# cube.net
KiCad netlist of a schematic drawn in Altium Designer
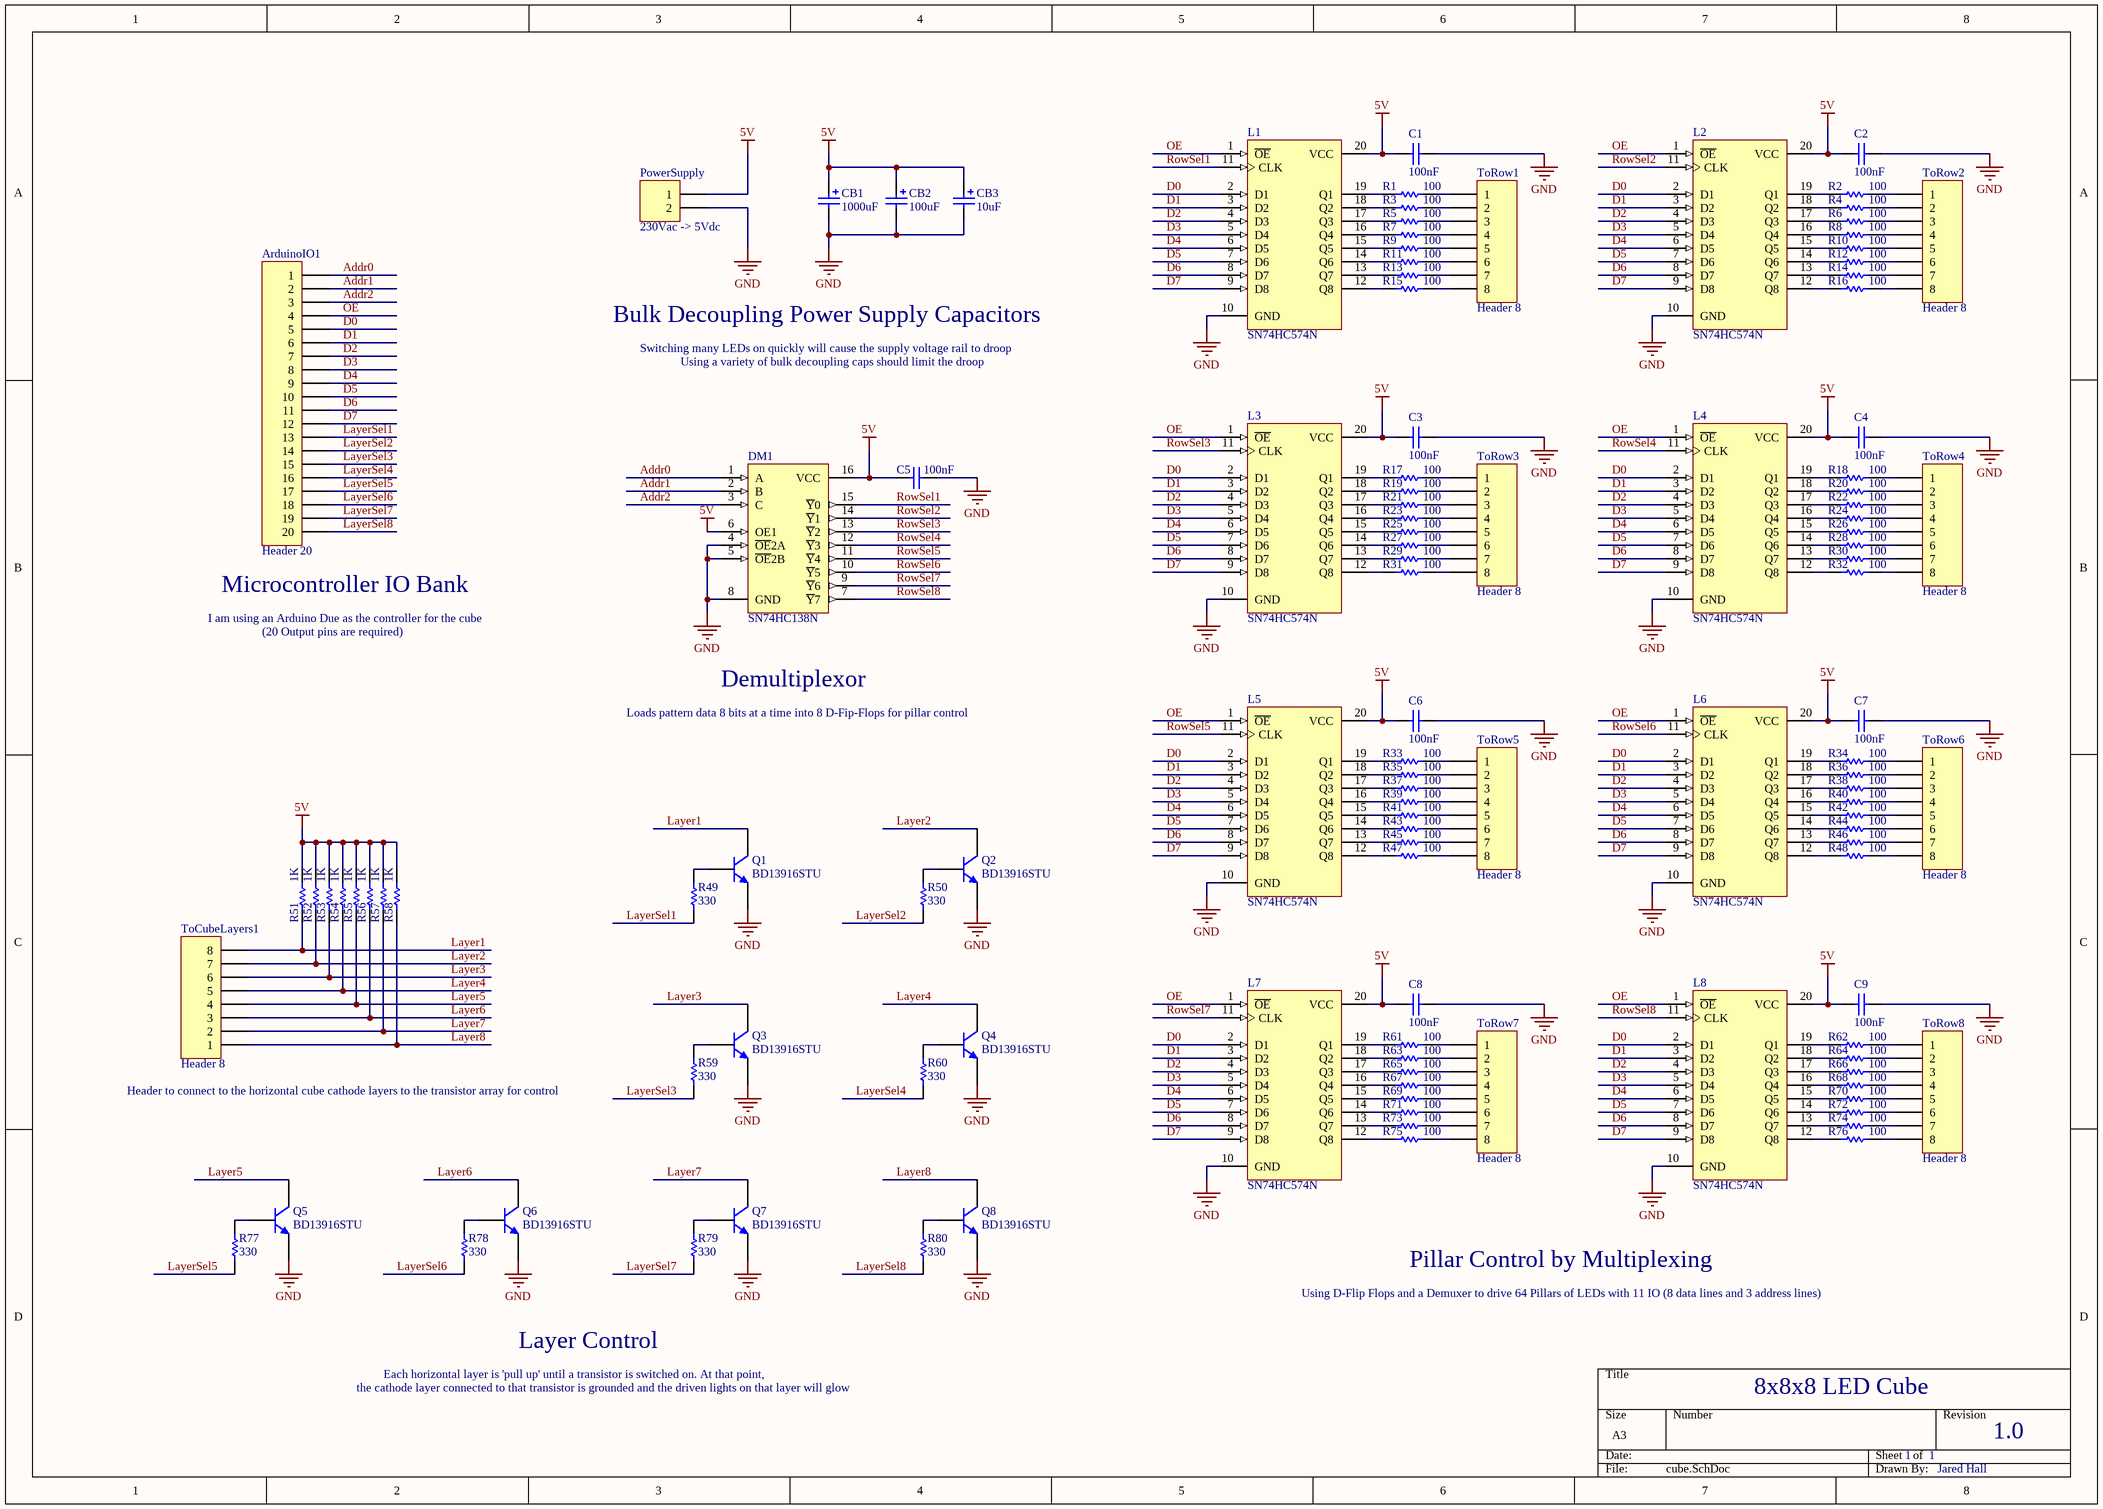
[diagram p0: cube.SchDoc]

(export (version "E")
  (design (tool "Eeschema 10.0.6"))
  (components
    (comp (ref "ArduinoIO1")
      (value "Header 20")
      (footprint "HDR1X20")
      (description "Header, 20-Pin")
      (fields (field (name "PUBLISHER") "Altium Limited"))
      (libsource (lib "Miscellaneous Connectors") (part "Header 20"))
    )
    (comp (ref "C1")
      (value "100nF")
      (footprint "RAD-0.3")
      (description "Capacitor")
      (fields (field (name "Comment") "Cap") (field (name "PUBLISHER") "Altium Limited"))
      (libsource (lib "Miscellaneous Devices") (part "Cap"))
    )
    (comp (ref "C2")
      (value "100nF")
      (footprint "RAD-0.3")
      (description "Capacitor")
      (fields (field (name "Comment") "Cap") (field (name "PUBLISHER") "Altium Limited"))
      (libsource (lib "Miscellaneous Devices") (part "Cap"))
    )
    (comp (ref "C3")
      (value "100nF")
      (footprint "RAD-0.3")
      (description "Capacitor")
      (fields (field (name "Comment") "Cap") (field (name "PUBLISHER") "Altium Limited"))
      (libsource (lib "Miscellaneous Devices") (part "Cap"))
    )
    (comp (ref "C4")
      (value "100nF")
      (footprint "RAD-0.3")
      (description "Capacitor")
      (fields (field (name "Comment") "Cap") (field (name "PUBLISHER") "Altium Limited"))
      (libsource (lib "Miscellaneous Devices") (part "Cap"))
    )
    (comp (ref "C5")
      (value "100nF")
      (footprint "RAD-0.3")
      (description "Capacitor")
      (fields (field (name "Comment") "Cap") (field (name "PUBLISHER") "Altium Limited"))
      (libsource (lib "Miscellaneous Devices") (part "Cap"))
    )
    (comp (ref "C6")
      (value "100nF")
      (footprint "RAD-0.3")
      (description "Capacitor")
      (fields (field (name "Comment") "Cap") (field (name "PUBLISHER") "Altium Limited"))
      (libsource (lib "Miscellaneous Devices") (part "Cap"))
    )
    (comp (ref "C7")
      (value "100nF")
      (footprint "RAD-0.3")
      (description "Capacitor")
      (fields (field (name "Comment") "Cap") (field (name "PUBLISHER") "Altium Limited"))
      (libsource (lib "Miscellaneous Devices") (part "Cap"))
    )
    (comp (ref "C8")
      (value "100nF")
      (footprint "RAD-0.3")
      (description "Capacitor")
      (fields (field (name "Comment") "Cap") (field (name "PUBLISHER") "Altium Limited"))
      (libsource (lib "Miscellaneous Devices") (part "Cap"))
    )
    (comp (ref "C9")
      (value "100nF")
      (footprint "RAD-0.3")
      (description "Capacitor")
      (fields (field (name "Comment") "Cap") (field (name "PUBLISHER") "Altium Limited"))
      (libsource (lib "Miscellaneous Devices") (part "Cap"))
    )
    (comp (ref "CB1")
      (value "1000uF")
      (footprint "POLAR0.8")
      (description "Polarized Capacitor (Axial)")
      (fields (field (name "Comment") "Cap Pol2") (field (name "PUBLISHER") "Altium Limited"))
      (libsource (lib "Miscellaneous Devices") (part "Cap Pol2"))
    )
    (comp (ref "CB2")
      (value "100uF")
      (footprint "POLAR0.8")
      (description "Polarized Capacitor (Axial)")
      (fields (field (name "Comment") "Cap Pol2") (field (name "PUBLISHER") "Altium Limited"))
      (libsource (lib "Miscellaneous Devices") (part "Cap Pol2"))
    )
    (comp (ref "CB3")
      (value "10uF")
      (footprint "POLAR0.8")
      (description "Polarized Capacitor (Axial)")
      (fields (field (name "Comment") "Cap Pol2") (field (name "PUBLISHER") "Altium Limited"))
      (libsource (lib "Miscellaneous Devices") (part "Cap Pol2"))
    )
    (comp (ref "DM1")
      (value "SN74HC138N")
      (footprint "N016")
      (description "3-Line to 8-Line Decoder / Demultiplexer")
      (fields (field (name "PUBLISHER") "Altium Limited"))
      (libsource (lib "TI Logic Decoder Demux") (part "SN74HC138N"))
    )
    (comp (ref "L1")
      (value "SN74HC574N")
      (footprint "N020")
      (description "Octal Edge-Triggered D-Type Flip-Flop with 3-State Outputs")
      (fields (field (name "PUBLISHER") "Altium Limited"))
      (libsource (lib "TI Logic Flip-Flop") (part "SN74HC574N"))
    )
    (comp (ref "L2")
      (value "SN74HC574N")
      (footprint "N020")
      (description "Octal Edge-Triggered D-Type Flip-Flop with 3-State Outputs")
      (fields (field (name "PUBLISHER") "Altium Limited"))
      (libsource (lib "TI Logic Flip-Flop") (part "SN74HC574N"))
    )
    (comp (ref "L3")
      (value "SN74HC574N")
      (footprint "N020")
      (description "Octal Edge-Triggered D-Type Flip-Flop with 3-State Outputs")
      (fields (field (name "PUBLISHER") "Altium Limited"))
      (libsource (lib "TI Logic Flip-Flop") (part "SN74HC574N"))
    )
    (comp (ref "L4")
      (value "SN74HC574N")
      (footprint "N020")
      (description "Octal Edge-Triggered D-Type Flip-Flop with 3-State Outputs")
      (fields (field (name "PUBLISHER") "Altium Limited"))
      (libsource (lib "TI Logic Flip-Flop") (part "SN74HC574N"))
    )
    (comp (ref "L5")
      (value "SN74HC574N")
      (footprint "N020")
      (description "Octal Edge-Triggered D-Type Flip-Flop with 3-State Outputs")
      (fields (field (name "PUBLISHER") "Altium Limited"))
      (libsource (lib "TI Logic Flip-Flop") (part "SN74HC574N"))
    )
    (comp (ref "L6")
      (value "SN74HC574N")
      (footprint "N020")
      (description "Octal Edge-Triggered D-Type Flip-Flop with 3-State Outputs")
      (fields (field (name "PUBLISHER") "Altium Limited"))
      (libsource (lib "TI Logic Flip-Flop") (part "SN74HC574N"))
    )
    (comp (ref "L7")
      (value "SN74HC574N")
      (footprint "N020")
      (description "Octal Edge-Triggered D-Type Flip-Flop with 3-State Outputs")
      (fields (field (name "PUBLISHER") "Altium Limited"))
      (libsource (lib "TI Logic Flip-Flop") (part "SN74HC574N"))
    )
    (comp (ref "L8")
      (value "SN74HC574N")
      (footprint "N020")
      (description "Octal Edge-Triggered D-Type Flip-Flop with 3-State Outputs")
      (fields (field (name "PUBLISHER") "Altium Limited"))
      (libsource (lib "TI Logic Flip-Flop") (part "SN74HC574N"))
    )
    (comp (ref "PowerSupply")
      (value "230Vac -> 5Vdc")
      (footprint "HDR1X2")
      (description "Header, 2-Pin")
      (fields (field (name "PUBLISHER") "Altium Limited"))
      (libsource (lib "Miscellaneous Connectors") (part "Header 2"))
    )
    (comp (ref "Q1")
      (value "BD13916STU")
      (footprint "TO-226-AA")
      (description "NPN Bipolar Transistor")
      (fields (field (name "PUBLISHER") "Altium Limited"))
      (libsource (lib "Miscellaneous Devices") (part "NPN"))
    )
    (comp (ref "Q2")
      (value "BD13916STU")
      (footprint "TO-226-AA")
      (description "NPN Bipolar Transistor")
      (fields (field (name "PUBLISHER") "Altium Limited"))
      (libsource (lib "Miscellaneous Devices") (part "NPN"))
    )
    (comp (ref "Q3")
      (value "BD13916STU")
      (footprint "TO-226-AA")
      (description "NPN Bipolar Transistor")
      (fields (field (name "PUBLISHER") "Altium Limited"))
      (libsource (lib "Miscellaneous Devices") (part "NPN"))
    )
    (comp (ref "Q4")
      (value "BD13916STU")
      (footprint "TO-226-AA")
      (description "NPN Bipolar Transistor")
      (fields (field (name "PUBLISHER") "Altium Limited"))
      (libsource (lib "Miscellaneous Devices") (part "NPN"))
    )
    (comp (ref "Q5")
      (value "BD13916STU")
      (footprint "TO-226-AA")
      (description "NPN Bipolar Transistor")
      (fields (field (name "PUBLISHER") "Altium Limited"))
      (libsource (lib "Miscellaneous Devices") (part "NPN"))
    )
    (comp (ref "Q6")
      (value "BD13916STU")
      (footprint "TO-226-AA")
      (description "NPN Bipolar Transistor")
      (fields (field (name "PUBLISHER") "Altium Limited"))
      (libsource (lib "Miscellaneous Devices") (part "NPN"))
    )
    (comp (ref "Q7")
      (value "BD13916STU")
      (footprint "TO-226-AA")
      (description "NPN Bipolar Transistor")
      (fields (field (name "PUBLISHER") "Altium Limited"))
      (libsource (lib "Miscellaneous Devices") (part "NPN"))
    )
    (comp (ref "Q8")
      (value "BD13916STU")
      (footprint "TO-226-AA")
      (description "NPN Bipolar Transistor")
      (fields (field (name "PUBLISHER") "Altium Limited"))
      (libsource (lib "Miscellaneous Devices") (part "NPN"))
    )
    (comp (ref "R1")
      (value "100")
      (footprint "AXIAL-0.3")
      (description "Resistor")
      (fields (field (name "Comment") "Res1") (field (name "PUBLISHER") "Altium Limited"))
      (libsource (lib "Miscellaneous Devices") (part "Res1"))
    )
    (comp (ref "R2")
      (value "100")
      (footprint "AXIAL-0.3")
      (description "Resistor")
      (fields (field (name "Comment") "Res1") (field (name "PUBLISHER") "Altium Limited"))
      (libsource (lib "Miscellaneous Devices") (part "Res1"))
    )
    (comp (ref "R3")
      (value "100")
      (footprint "AXIAL-0.3")
      (description "Resistor")
      (fields (field (name "Comment") "Res1") (field (name "PUBLISHER") "Altium Limited"))
      (libsource (lib "Miscellaneous Devices") (part "Res1"))
    )
    (comp (ref "R4")
      (value "100")
      (footprint "AXIAL-0.3")
      (description "Resistor")
      (fields (field (name "Comment") "Res1") (field (name "PUBLISHER") "Altium Limited"))
      (libsource (lib "Miscellaneous Devices") (part "Res1"))
    )
    (comp (ref "R5")
      (value "100")
      (footprint "AXIAL-0.3")
      (description "Resistor")
      (fields (field (name "Comment") "Res1") (field (name "PUBLISHER") "Altium Limited"))
      (libsource (lib "Miscellaneous Devices") (part "Res1"))
    )
    (comp (ref "R6")
      (value "100")
      (footprint "AXIAL-0.3")
      (description "Resistor")
      (fields (field (name "Comment") "Res1") (field (name "PUBLISHER") "Altium Limited"))
      (libsource (lib "Miscellaneous Devices") (part "Res1"))
    )
    (comp (ref "R7")
      (value "100")
      (footprint "AXIAL-0.3")
      (description "Resistor")
      (fields (field (name "Comment") "Res1") (field (name "PUBLISHER") "Altium Limited"))
      (libsource (lib "Miscellaneous Devices") (part "Res1"))
    )
    (comp (ref "R8")
      (value "100")
      (footprint "AXIAL-0.3")
      (description "Resistor")
      (fields (field (name "Comment") "Res1") (field (name "PUBLISHER") "Altium Limited"))
      (libsource (lib "Miscellaneous Devices") (part "Res1"))
    )
    (comp (ref "R9")
      (value "100")
      (footprint "AXIAL-0.3")
      (description "Resistor")
      (fields (field (name "Comment") "Res1") (field (name "PUBLISHER") "Altium Limited"))
      (libsource (lib "Miscellaneous Devices") (part "Res1"))
    )
    (comp (ref "R10")
      (value "100")
      (footprint "AXIAL-0.3")
      (description "Resistor")
      (fields (field (name "Comment") "Res1") (field (name "PUBLISHER") "Altium Limited"))
      (libsource (lib "Miscellaneous Devices") (part "Res1"))
    )
    (comp (ref "R11")
      (value "100")
      (footprint "AXIAL-0.3")
      (description "Resistor")
      (fields (field (name "Comment") "Res1") (field (name "PUBLISHER") "Altium Limited"))
      (libsource (lib "Miscellaneous Devices") (part "Res1"))
    )
    (comp (ref "R12")
      (value "100")
      (footprint "AXIAL-0.3")
      (description "Resistor")
      (fields (field (name "Comment") "Res1") (field (name "PUBLISHER") "Altium Limited"))
      (libsource (lib "Miscellaneous Devices") (part "Res1"))
    )
    (comp (ref "R13")
      (value "100")
      (footprint "AXIAL-0.3")
      (description "Resistor")
      (fields (field (name "Comment") "Res1") (field (name "PUBLISHER") "Altium Limited"))
      (libsource (lib "Miscellaneous Devices") (part "Res1"))
    )
    (comp (ref "R14")
      (value "100")
      (footprint "AXIAL-0.3")
      (description "Resistor")
      (fields (field (name "Comment") "Res1") (field (name "PUBLISHER") "Altium Limited"))
      (libsource (lib "Miscellaneous Devices") (part "Res1"))
    )
    (comp (ref "R15")
      (value "100")
      (footprint "AXIAL-0.3")
      (description "Resistor")
      (fields (field (name "Comment") "Res1") (field (name "PUBLISHER") "Altium Limited"))
      (libsource (lib "Miscellaneous Devices") (part "Res1"))
    )
    (comp (ref "R16")
      (value "100")
      (footprint "AXIAL-0.3")
      (description "Resistor")
      (fields (field (name "Comment") "Res1") (field (name "PUBLISHER") "Altium Limited"))
      (libsource (lib "Miscellaneous Devices") (part "Res1"))
    )
    (comp (ref "R17")
      (value "100")
      (footprint "AXIAL-0.3")
      (description "Resistor")
      (fields (field (name "Comment") "Res1") (field (name "PUBLISHER") "Altium Limited"))
      (libsource (lib "Miscellaneous Devices") (part "Res1"))
    )
    (comp (ref "R18")
      (value "100")
      (footprint "AXIAL-0.3")
      (description "Resistor")
      (fields (field (name "Comment") "Res1") (field (name "PUBLISHER") "Altium Limited"))
      (libsource (lib "Miscellaneous Devices") (part "Res1"))
    )
    (comp (ref "R19")
      (value "100")
      (footprint "AXIAL-0.3")
      (description "Resistor")
      (fields (field (name "Comment") "Res1") (field (name "PUBLISHER") "Altium Limited"))
      (libsource (lib "Miscellaneous Devices") (part "Res1"))
    )
    (comp (ref "R20")
      (value "100")
      (footprint "AXIAL-0.3")
      (description "Resistor")
      (fields (field (name "Comment") "Res1") (field (name "PUBLISHER") "Altium Limited"))
      (libsource (lib "Miscellaneous Devices") (part "Res1"))
    )
    (comp (ref "R21")
      (value "100")
      (footprint "AXIAL-0.3")
      (description "Resistor")
      (fields (field (name "Comment") "Res1") (field (name "PUBLISHER") "Altium Limited"))
      (libsource (lib "Miscellaneous Devices") (part "Res1"))
    )
    (comp (ref "R22")
      (value "100")
      (footprint "AXIAL-0.3")
      (description "Resistor")
      (fields (field (name "Comment") "Res1") (field (name "PUBLISHER") "Altium Limited"))
      (libsource (lib "Miscellaneous Devices") (part "Res1"))
    )
    (comp (ref "R23")
      (value "100")
      (footprint "AXIAL-0.3")
      (description "Resistor")
      (fields (field (name "Comment") "Res1") (field (name "PUBLISHER") "Altium Limited"))
      (libsource (lib "Miscellaneous Devices") (part "Res1"))
    )
    (comp (ref "R24")
      (value "100")
      (footprint "AXIAL-0.3")
      (description "Resistor")
      (fields (field (name "Comment") "Res1") (field (name "PUBLISHER") "Altium Limited"))
      (libsource (lib "Miscellaneous Devices") (part "Res1"))
    )
    (comp (ref "R25")
      (value "100")
      (footprint "AXIAL-0.3")
      (description "Resistor")
      (fields (field (name "Comment") "Res1") (field (name "PUBLISHER") "Altium Limited"))
      (libsource (lib "Miscellaneous Devices") (part "Res1"))
    )
    (comp (ref "R26")
      (value "100")
      (footprint "AXIAL-0.3")
      (description "Resistor")
      (fields (field (name "Comment") "Res1") (field (name "PUBLISHER") "Altium Limited"))
      (libsource (lib "Miscellaneous Devices") (part "Res1"))
    )
    (comp (ref "R27")
      (value "100")
      (footprint "AXIAL-0.3")
      (description "Resistor")
      (fields (field (name "Comment") "Res1") (field (name "PUBLISHER") "Altium Limited"))
      (libsource (lib "Miscellaneous Devices") (part "Res1"))
    )
    (comp (ref "R28")
      (value "100")
      (footprint "AXIAL-0.3")
      (description "Resistor")
      (fields (field (name "Comment") "Res1") (field (name "PUBLISHER") "Altium Limited"))
      (libsource (lib "Miscellaneous Devices") (part "Res1"))
    )
    (comp (ref "R29")
      (value "100")
      (footprint "AXIAL-0.3")
      (description "Resistor")
      (fields (field (name "Comment") "Res1") (field (name "PUBLISHER") "Altium Limited"))
      (libsource (lib "Miscellaneous Devices") (part "Res1"))
    )
    (comp (ref "R30")
      (value "100")
      (footprint "AXIAL-0.3")
      (description "Resistor")
      (fields (field (name "Comment") "Res1") (field (name "PUBLISHER") "Altium Limited"))
      (libsource (lib "Miscellaneous Devices") (part "Res1"))
    )
    (comp (ref "R31")
      (value "100")
      (footprint "AXIAL-0.3")
      (description "Resistor")
      (fields (field (name "Comment") "Res1") (field (name "PUBLISHER") "Altium Limited"))
      (libsource (lib "Miscellaneous Devices") (part "Res1"))
    )
    (comp (ref "R32")
      (value "100")
      (footprint "AXIAL-0.3")
      (description "Resistor")
      (fields (field (name "Comment") "Res1") (field (name "PUBLISHER") "Altium Limited"))
      (libsource (lib "Miscellaneous Devices") (part "Res1"))
    )
    (comp (ref "R33")
      (value "100")
      (footprint "AXIAL-0.3")
      (description "Resistor")
      (fields (field (name "Comment") "Res1") (field (name "PUBLISHER") "Altium Limited"))
      (libsource (lib "Miscellaneous Devices") (part "Res1"))
    )
    (comp (ref "R34")
      (value "100")
      (footprint "AXIAL-0.3")
      (description "Resistor")
      (fields (field (name "Comment") "Res1") (field (name "PUBLISHER") "Altium Limited"))
      (libsource (lib "Miscellaneous Devices") (part "Res1"))
    )
    (comp (ref "R35")
      (value "100")
      (footprint "AXIAL-0.3")
      (description "Resistor")
      (fields (field (name "Comment") "Res1") (field (name "PUBLISHER") "Altium Limited"))
      (libsource (lib "Miscellaneous Devices") (part "Res1"))
    )
    (comp (ref "R36")
      (value "100")
      (footprint "AXIAL-0.3")
      (description "Resistor")
      (fields (field (name "Comment") "Res1") (field (name "PUBLISHER") "Altium Limited"))
      (libsource (lib "Miscellaneous Devices") (part "Res1"))
    )
    (comp (ref "R37")
      (value "100")
      (footprint "AXIAL-0.3")
      (description "Resistor")
      (fields (field (name "Comment") "Res1") (field (name "PUBLISHER") "Altium Limited"))
      (libsource (lib "Miscellaneous Devices") (part "Res1"))
    )
    (comp (ref "R38")
      (value "100")
      (footprint "AXIAL-0.3")
      (description "Resistor")
      (fields (field (name "Comment") "Res1") (field (name "PUBLISHER") "Altium Limited"))
      (libsource (lib "Miscellaneous Devices") (part "Res1"))
    )
    (comp (ref "R39")
      (value "100")
      (footprint "AXIAL-0.3")
      (description "Resistor")
      (fields (field (name "Comment") "Res1") (field (name "PUBLISHER") "Altium Limited"))
      (libsource (lib "Miscellaneous Devices") (part "Res1"))
    )
    (comp (ref "R40")
      (value "100")
      (footprint "AXIAL-0.3")
      (description "Resistor")
      (fields (field (name "Comment") "Res1") (field (name "PUBLISHER") "Altium Limited"))
      (libsource (lib "Miscellaneous Devices") (part "Res1"))
    )
    (comp (ref "R41")
      (value "100")
      (footprint "AXIAL-0.3")
      (description "Resistor")
      (fields (field (name "Comment") "Res1") (field (name "PUBLISHER") "Altium Limited"))
      (libsource (lib "Miscellaneous Devices") (part "Res1"))
    )
    (comp (ref "R42")
      (value "100")
      (footprint "AXIAL-0.3")
      (description "Resistor")
      (fields (field (name "Comment") "Res1") (field (name "PUBLISHER") "Altium Limited"))
      (libsource (lib "Miscellaneous Devices") (part "Res1"))
    )
    (comp (ref "R43")
      (value "100")
      (footprint "AXIAL-0.3")
      (description "Resistor")
      (fields (field (name "Comment") "Res1") (field (name "PUBLISHER") "Altium Limited"))
      (libsource (lib "Miscellaneous Devices") (part "Res1"))
    )
    (comp (ref "R44")
      (value "100")
      (footprint "AXIAL-0.3")
      (description "Resistor")
      (fields (field (name "Comment") "Res1") (field (name "PUBLISHER") "Altium Limited"))
      (libsource (lib "Miscellaneous Devices") (part "Res1"))
    )
    (comp (ref "R45")
      (value "100")
      (footprint "AXIAL-0.3")
      (description "Resistor")
      (fields (field (name "Comment") "Res1") (field (name "PUBLISHER") "Altium Limited"))
      (libsource (lib "Miscellaneous Devices") (part "Res1"))
    )
    (comp (ref "R46")
      (value "100")
      (footprint "AXIAL-0.3")
      (description "Resistor")
      (fields (field (name "Comment") "Res1") (field (name "PUBLISHER") "Altium Limited"))
      (libsource (lib "Miscellaneous Devices") (part "Res1"))
    )
    (comp (ref "R47")
      (value "100")
      (footprint "AXIAL-0.3")
      (description "Resistor")
      (fields (field (name "Comment") "Res1") (field (name "PUBLISHER") "Altium Limited"))
      (libsource (lib "Miscellaneous Devices") (part "Res1"))
    )
    (comp (ref "R48")
      (value "100")
      (footprint "AXIAL-0.3")
      (description "Resistor")
      (fields (field (name "Comment") "Res1") (field (name "PUBLISHER") "Altium Limited"))
      (libsource (lib "Miscellaneous Devices") (part "Res1"))
    )
    (comp (ref "R49")
      (value "330")
      (footprint "AXIAL-0.3")
      (description "Resistor")
      (fields (field (name "Comment") "Res1") (field (name "PUBLISHER") "Altium Limited"))
      (libsource (lib "Miscellaneous Devices") (part "Res1"))
    )
    (comp (ref "R50")
      (value "330")
      (footprint "AXIAL-0.3")
      (description "Resistor")
      (fields (field (name "Comment") "Res1") (field (name "PUBLISHER") "Altium Limited"))
      (libsource (lib "Miscellaneous Devices") (part "Res1"))
    )
    (comp (ref "R51")
      (value "1K")
      (footprint "AXIAL-0.3")
      (description "Resistor")
      (fields (field (name "Comment") "Res1") (field (name "PUBLISHER") "Altium Limited"))
      (libsource (lib "Miscellaneous Devices") (part "Res1"))
    )
    (comp (ref "R52")
      (value "1K")
      (footprint "AXIAL-0.3")
      (description "Resistor")
      (fields (field (name "Comment") "Res1") (field (name "PUBLISHER") "Altium Limited"))
      (libsource (lib "Miscellaneous Devices") (part "Res1"))
    )
    (comp (ref "R53")
      (value "1K")
      (footprint "AXIAL-0.3")
      (description "Resistor")
      (fields (field (name "Comment") "Res1") (field (name "PUBLISHER") "Altium Limited"))
      (libsource (lib "Miscellaneous Devices") (part "Res1"))
    )
    (comp (ref "R54")
      (value "1K")
      (footprint "AXIAL-0.3")
      (description "Resistor")
      (fields (field (name "Comment") "Res1") (field (name "PUBLISHER") "Altium Limited"))
      (libsource (lib "Miscellaneous Devices") (part "Res1"))
    )
    (comp (ref "R55")
      (value "1K")
      (footprint "AXIAL-0.3")
      (description "Resistor")
      (fields (field (name "Comment") "Res1") (field (name "PUBLISHER") "Altium Limited"))
      (libsource (lib "Miscellaneous Devices") (part "Res1"))
    )
    (comp (ref "R56")
      (value "1K")
      (footprint "AXIAL-0.3")
      (description "Resistor")
      (fields (field (name "Comment") "Res1") (field (name "PUBLISHER") "Altium Limited"))
      (libsource (lib "Miscellaneous Devices") (part "Res1"))
    )
    (comp (ref "R57")
      (value "1K")
      (footprint "AXIAL-0.3")
      (description "Resistor")
      (fields (field (name "Comment") "Res1") (field (name "PUBLISHER") "Altium Limited"))
      (libsource (lib "Miscellaneous Devices") (part "Res1"))
    )
    (comp (ref "R58")
      (value "1K")
      (footprint "AXIAL-0.3")
      (description "Resistor")
      (fields (field (name "Comment") "Res1") (field (name "PUBLISHER") "Altium Limited"))
      (libsource (lib "Miscellaneous Devices") (part "Res1"))
    )
    (comp (ref "R59")
      (value "330")
      (footprint "AXIAL-0.3")
      (description "Resistor")
      (fields (field (name "Comment") "Res1") (field (name "PUBLISHER") "Altium Limited"))
      (libsource (lib "Miscellaneous Devices") (part "Res1"))
    )
    (comp (ref "R60")
      (value "330")
      (footprint "AXIAL-0.3")
      (description "Resistor")
      (fields (field (name "Comment") "Res1") (field (name "PUBLISHER") "Altium Limited"))
      (libsource (lib "Miscellaneous Devices") (part "Res1"))
    )
    (comp (ref "R61")
      (value "100")
      (footprint "AXIAL-0.3")
      (description "Resistor")
      (fields (field (name "Comment") "Res1") (field (name "PUBLISHER") "Altium Limited"))
      (libsource (lib "Miscellaneous Devices") (part "Res1"))
    )
    (comp (ref "R62")
      (value "100")
      (footprint "AXIAL-0.3")
      (description "Resistor")
      (fields (field (name "Comment") "Res1") (field (name "PUBLISHER") "Altium Limited"))
      (libsource (lib "Miscellaneous Devices") (part "Res1"))
    )
    (comp (ref "R63")
      (value "100")
      (footprint "AXIAL-0.3")
      (description "Resistor")
      (fields (field (name "Comment") "Res1") (field (name "PUBLISHER") "Altium Limited"))
      (libsource (lib "Miscellaneous Devices") (part "Res1"))
    )
    (comp (ref "R64")
      (value "100")
      (footprint "AXIAL-0.3")
      (description "Resistor")
      (fields (field (name "Comment") "Res1") (field (name "PUBLISHER") "Altium Limited"))
      (libsource (lib "Miscellaneous Devices") (part "Res1"))
    )
    (comp (ref "R65")
      (value "100")
      (footprint "AXIAL-0.3")
      (description "Resistor")
      (fields (field (name "Comment") "Res1") (field (name "PUBLISHER") "Altium Limited"))
      (libsource (lib "Miscellaneous Devices") (part "Res1"))
    )
    (comp (ref "R66")
      (value "100")
      (footprint "AXIAL-0.3")
      (description "Resistor")
      (fields (field (name "Comment") "Res1") (field (name "PUBLISHER") "Altium Limited"))
      (libsource (lib "Miscellaneous Devices") (part "Res1"))
    )
    (comp (ref "R67")
      (value "100")
      (footprint "AXIAL-0.3")
      (description "Resistor")
      (fields (field (name "Comment") "Res1") (field (name "PUBLISHER") "Altium Limited"))
      (libsource (lib "Miscellaneous Devices") (part "Res1"))
    )
    (comp (ref "R68")
      (value "100")
      (footprint "AXIAL-0.3")
      (description "Resistor")
      (fields (field (name "Comment") "Res1") (field (name "PUBLISHER") "Altium Limited"))
      (libsource (lib "Miscellaneous Devices") (part "Res1"))
    )
    (comp (ref "R69")
      (value "100")
      (footprint "AXIAL-0.3")
      (description "Resistor")
      (fields (field (name "Comment") "Res1") (field (name "PUBLISHER") "Altium Limited"))
      (libsource (lib "Miscellaneous Devices") (part "Res1"))
    )
    (comp (ref "R70")
      (value "100")
      (footprint "AXIAL-0.3")
      (description "Resistor")
      (fields (field (name "Comment") "Res1") (field (name "PUBLISHER") "Altium Limited"))
      (libsource (lib "Miscellaneous Devices") (part "Res1"))
    )
    (comp (ref "R71")
      (value "100")
      (footprint "AXIAL-0.3")
      (description "Resistor")
      (fields (field (name "Comment") "Res1") (field (name "PUBLISHER") "Altium Limited"))
      (libsource (lib "Miscellaneous Devices") (part "Res1"))
    )
    (comp (ref "R72")
      (value "100")
      (footprint "AXIAL-0.3")
      (description "Resistor")
      (fields (field (name "Comment") "Res1") (field (name "PUBLISHER") "Altium Limited"))
      (libsource (lib "Miscellaneous Devices") (part "Res1"))
    )
    (comp (ref "R73")
      (value "100")
      (footprint "AXIAL-0.3")
      (description "Resistor")
      (fields (field (name "Comment") "Res1") (field (name "PUBLISHER") "Altium Limited"))
      (libsource (lib "Miscellaneous Devices") (part "Res1"))
    )
    (comp (ref "R74")
      (value "100")
      (footprint "AXIAL-0.3")
      (description "Resistor")
      (fields (field (name "Comment") "Res1") (field (name "PUBLISHER") "Altium Limited"))
      (libsource (lib "Miscellaneous Devices") (part "Res1"))
    )
    (comp (ref "R75")
      (value "100")
      (footprint "AXIAL-0.3")
      (description "Resistor")
      (fields (field (name "Comment") "Res1") (field (name "PUBLISHER") "Altium Limited"))
      (libsource (lib "Miscellaneous Devices") (part "Res1"))
    )
    (comp (ref "R76")
      (value "100")
      (footprint "AXIAL-0.3")
      (description "Resistor")
      (fields (field (name "Comment") "Res1") (field (name "PUBLISHER") "Altium Limited"))
      (libsource (lib "Miscellaneous Devices") (part "Res1"))
    )
    (comp (ref "R77")
      (value "330")
      (footprint "AXIAL-0.3")
      (description "Resistor")
      (fields (field (name "Comment") "Res1") (field (name "PUBLISHER") "Altium Limited"))
      (libsource (lib "Miscellaneous Devices") (part "Res1"))
    )
    (comp (ref "R78")
      (value "330")
      (footprint "AXIAL-0.3")
      (description "Resistor")
      (fields (field (name "Comment") "Res1") (field (name "PUBLISHER") "Altium Limited"))
      (libsource (lib "Miscellaneous Devices") (part "Res1"))
    )
    (comp (ref "R79")
      (value "330")
      (footprint "AXIAL-0.3")
      (description "Resistor")
      (fields (field (name "Comment") "Res1") (field (name "PUBLISHER") "Altium Limited"))
      (libsource (lib "Miscellaneous Devices") (part "Res1"))
    )
    (comp (ref "R80")
      (value "330")
      (footprint "AXIAL-0.3")
      (description "Resistor")
      (fields (field (name "Comment") "Res1") (field (name "PUBLISHER") "Altium Limited"))
      (libsource (lib "Miscellaneous Devices") (part "Res1"))
    )
    (comp (ref "ToCubeLayers1")
      (value "Header 8")
      (footprint "HDR1X8")
      (description "Header, 8-Pin")
      (fields (field (name "PUBLISHER") "Altium Limited"))
      (libsource (lib "") (part "Header 8_1"))
    )
    (comp (ref "ToRow1")
      (value "Header 8")
      (footprint "HDR1X8")
      (description "Header, 8-Pin")
      (fields (field (name "PUBLISHER") "Altium Limited"))
      (libsource (lib "Miscellaneous Connectors") (part "Header 8"))
    )
    (comp (ref "ToRow2")
      (value "Header 8")
      (footprint "HDR1X8")
      (description "Header, 8-Pin")
      (fields (field (name "PUBLISHER") "Altium Limited"))
      (libsource (lib "Miscellaneous Connectors") (part "Header 8"))
    )
    (comp (ref "ToRow3")
      (value "Header 8")
      (footprint "HDR1X8")
      (description "Header, 8-Pin")
      (fields (field (name "PUBLISHER") "Altium Limited"))
      (libsource (lib "Miscellaneous Connectors") (part "Header 8"))
    )
    (comp (ref "ToRow4")
      (value "Header 8")
      (footprint "HDR1X8")
      (description "Header, 8-Pin")
      (fields (field (name "PUBLISHER") "Altium Limited"))
      (libsource (lib "Miscellaneous Connectors") (part "Header 8"))
    )
    (comp (ref "ToRow5")
      (value "Header 8")
      (footprint "HDR1X8")
      (description "Header, 8-Pin")
      (fields (field (name "PUBLISHER") "Altium Limited"))
      (libsource (lib "Miscellaneous Connectors") (part "Header 8"))
    )
    (comp (ref "ToRow6")
      (value "Header 8")
      (footprint "HDR1X8")
      (description "Header, 8-Pin")
      (fields (field (name "PUBLISHER") "Altium Limited"))
      (libsource (lib "Miscellaneous Connectors") (part "Header 8"))
    )
    (comp (ref "ToRow7")
      (value "Header 8")
      (footprint "HDR1X8")
      (description "Header, 8-Pin")
      (fields (field (name "PUBLISHER") "Altium Limited"))
      (libsource (lib "Miscellaneous Connectors") (part "Header 8"))
    )
    (comp (ref "ToRow8")
      (value "Header 8")
      (footprint "HDR1X8")
      (description "Header, 8-Pin")
      (fields (field (name "PUBLISHER") "Altium Limited"))
      (libsource (lib "Miscellaneous Connectors") (part "Header 8"))
    )
  )
  (nets
    (net (code "1") (name "/Addr0") (class "Default")
      (node (ref "ArduinoIO1") (pin "1") (pinfunction "1_1") (pintype "passive"))
      (node (ref "DM1") (pin "1") (pinfunction "A_1") (pintype "input"))
    )
    (net (code "2") (name "/Addr1") (class "Default")
      (node (ref "ArduinoIO1") (pin "2") (pinfunction "2_2") (pintype "passive"))
      (node (ref "DM1") (pin "2") (pinfunction "B_2") (pintype "input"))
    )
    (net (code "3") (name "/Addr2") (class "Default")
      (node (ref "ArduinoIO1") (pin "3") (pinfunction "3_3") (pintype "passive"))
      (node (ref "DM1") (pin "3") (pinfunction "C_3") (pintype "input"))
    )
    (net (code "4") (name "/D0") (class "Default")
      (node (ref "ArduinoIO1") (pin "5") (pinfunction "5_5") (pintype "passive"))
      (node (ref "L1") (pin "2") (pinfunction "D1_2") (pintype "input"))
      (node (ref "L2") (pin "2") (pinfunction "D1_2") (pintype "input"))
      (node (ref "L3") (pin "2") (pinfunction "D1_2") (pintype "input"))
      (node (ref "L4") (pin "2") (pinfunction "D1_2") (pintype "input"))
      (node (ref "L5") (pin "2") (pinfunction "D1_2") (pintype "input"))
      (node (ref "L6") (pin "2") (pinfunction "D1_2") (pintype "input"))
      (node (ref "L7") (pin "2") (pinfunction "D1_2") (pintype "input"))
      (node (ref "L8") (pin "2") (pinfunction "D1_2") (pintype "input"))
    )
    (net (code "5") (name "/D1") (class "Default")
      (node (ref "ArduinoIO1") (pin "6") (pinfunction "6_6") (pintype "passive"))
      (node (ref "L1") (pin "3") (pinfunction "D2_3") (pintype "input"))
      (node (ref "L2") (pin "3") (pinfunction "D2_3") (pintype "input"))
      (node (ref "L3") (pin "3") (pinfunction "D2_3") (pintype "input"))
      (node (ref "L4") (pin "3") (pinfunction "D2_3") (pintype "input"))
      (node (ref "L5") (pin "3") (pinfunction "D2_3") (pintype "input"))
      (node (ref "L6") (pin "3") (pinfunction "D2_3") (pintype "input"))
      (node (ref "L7") (pin "3") (pinfunction "D2_3") (pintype "input"))
      (node (ref "L8") (pin "3") (pinfunction "D2_3") (pintype "input"))
    )
    (net (code "6") (name "/D2") (class "Default")
      (node (ref "ArduinoIO1") (pin "7") (pinfunction "7_7") (pintype "passive"))
      (node (ref "L1") (pin "4") (pinfunction "D3_4") (pintype "input"))
      (node (ref "L2") (pin "4") (pinfunction "D3_4") (pintype "input"))
      (node (ref "L3") (pin "4") (pinfunction "D3_4") (pintype "input"))
      (node (ref "L4") (pin "4") (pinfunction "D3_4") (pintype "input"))
      (node (ref "L5") (pin "4") (pinfunction "D3_4") (pintype "input"))
      (node (ref "L6") (pin "4") (pinfunction "D3_4") (pintype "input"))
      (node (ref "L7") (pin "4") (pinfunction "D3_4") (pintype "input"))
      (node (ref "L8") (pin "4") (pinfunction "D3_4") (pintype "input"))
    )
    (net (code "7") (name "/D3") (class "Default")
      (node (ref "ArduinoIO1") (pin "8") (pinfunction "8_8") (pintype "passive"))
      (node (ref "L1") (pin "5") (pinfunction "D4_5") (pintype "input"))
      (node (ref "L2") (pin "5") (pinfunction "D4_5") (pintype "input"))
      (node (ref "L3") (pin "5") (pinfunction "D4_5") (pintype "input"))
      (node (ref "L4") (pin "5") (pinfunction "D4_5") (pintype "input"))
      (node (ref "L5") (pin "5") (pinfunction "D4_5") (pintype "input"))
      (node (ref "L6") (pin "5") (pinfunction "D4_5") (pintype "input"))
      (node (ref "L7") (pin "5") (pinfunction "D4_5") (pintype "input"))
      (node (ref "L8") (pin "5") (pinfunction "D4_5") (pintype "input"))
    )
    (net (code "8") (name "/D4") (class "Default")
      (node (ref "ArduinoIO1") (pin "9") (pinfunction "9_9") (pintype "passive"))
      (node (ref "L1") (pin "6") (pinfunction "D5_6") (pintype "input"))
      (node (ref "L2") (pin "6") (pinfunction "D5_6") (pintype "input"))
      (node (ref "L3") (pin "6") (pinfunction "D5_6") (pintype "input"))
      (node (ref "L4") (pin "6") (pinfunction "D5_6") (pintype "input"))
      (node (ref "L5") (pin "6") (pinfunction "D5_6") (pintype "input"))
      (node (ref "L6") (pin "6") (pinfunction "D5_6") (pintype "input"))
      (node (ref "L7") (pin "6") (pinfunction "D5_6") (pintype "input"))
      (node (ref "L8") (pin "6") (pinfunction "D5_6") (pintype "input"))
    )
    (net (code "9") (name "/D5") (class "Default")
      (node (ref "ArduinoIO1") (pin "10") (pinfunction "10_10") (pintype "passive"))
      (node (ref "L1") (pin "7") (pinfunction "D6_7") (pintype "input"))
      (node (ref "L2") (pin "7") (pinfunction "D6_7") (pintype "input"))
      (node (ref "L3") (pin "7") (pinfunction "D6_7") (pintype "input"))
      (node (ref "L4") (pin "7") (pinfunction "D6_7") (pintype "input"))
      (node (ref "L5") (pin "7") (pinfunction "D6_7") (pintype "input"))
      (node (ref "L6") (pin "7") (pinfunction "D6_7") (pintype "input"))
      (node (ref "L7") (pin "7") (pinfunction "D6_7") (pintype "input"))
      (node (ref "L8") (pin "7") (pinfunction "D6_7") (pintype "input"))
    )
    (net (code "10") (name "/D6") (class "Default")
      (node (ref "ArduinoIO1") (pin "11") (pinfunction "11_11") (pintype "passive"))
      (node (ref "L1") (pin "8") (pinfunction "D7_8") (pintype "input"))
      (node (ref "L2") (pin "8") (pinfunction "D7_8") (pintype "input"))
      (node (ref "L3") (pin "8") (pinfunction "D7_8") (pintype "input"))
      (node (ref "L4") (pin "8") (pinfunction "D7_8") (pintype "input"))
      (node (ref "L5") (pin "8") (pinfunction "D7_8") (pintype "input"))
      (node (ref "L6") (pin "8") (pinfunction "D7_8") (pintype "input"))
      (node (ref "L7") (pin "8") (pinfunction "D7_8") (pintype "input"))
      (node (ref "L8") (pin "8") (pinfunction "D7_8") (pintype "input"))
    )
    (net (code "11") (name "/D7") (class "Default")
      (node (ref "ArduinoIO1") (pin "12") (pinfunction "12_12") (pintype "passive"))
      (node (ref "L1") (pin "9") (pinfunction "D8_9") (pintype "input"))
      (node (ref "L2") (pin "9") (pinfunction "D8_9") (pintype "input"))
      (node (ref "L3") (pin "9") (pinfunction "D8_9") (pintype "input"))
      (node (ref "L4") (pin "9") (pinfunction "D8_9") (pintype "input"))
      (node (ref "L5") (pin "9") (pinfunction "D8_9") (pintype "input"))
      (node (ref "L6") (pin "9") (pinfunction "D8_9") (pintype "input"))
      (node (ref "L7") (pin "9") (pinfunction "D8_9") (pintype "input"))
      (node (ref "L8") (pin "9") (pinfunction "D8_9") (pintype "input"))
    )
    (net (code "12") (name "/Layer1") (class "Default")
      (node (ref "Q1") (pin "1") (pinfunction "C_1") (pintype "passive"))
      (node (ref "R51") (pin "1") (pinfunction "1_1") (pintype "passive"))
      (node (ref "ToCubeLayers1") (pin "8") (pinfunction "8_8") (pintype "passive"))
    )
    (net (code "13") (name "/Layer2") (class "Default")
      (node (ref "Q2") (pin "1") (pinfunction "C_1") (pintype "passive"))
      (node (ref "R52") (pin "1") (pinfunction "1_1") (pintype "passive"))
      (node (ref "ToCubeLayers1") (pin "7") (pinfunction "7_7") (pintype "passive"))
    )
    (net (code "14") (name "/Layer3") (class "Default")
      (node (ref "Q3") (pin "1") (pinfunction "C_1") (pintype "passive"))
      (node (ref "R53") (pin "1") (pinfunction "1_1") (pintype "passive"))
      (node (ref "ToCubeLayers1") (pin "6") (pinfunction "6_6") (pintype "passive"))
    )
    (net (code "15") (name "/Layer4") (class "Default")
      (node (ref "Q4") (pin "1") (pinfunction "C_1") (pintype "passive"))
      (node (ref "R54") (pin "1") (pinfunction "1_1") (pintype "passive"))
      (node (ref "ToCubeLayers1") (pin "5") (pinfunction "5_5") (pintype "passive"))
    )
    (net (code "16") (name "/Layer5") (class "Default")
      (node (ref "Q5") (pin "1") (pinfunction "C_1") (pintype "passive"))
      (node (ref "R55") (pin "1") (pinfunction "1_1") (pintype "passive"))
      (node (ref "ToCubeLayers1") (pin "4") (pinfunction "4_4") (pintype "passive"))
    )
    (net (code "17") (name "/Layer6") (class "Default")
      (node (ref "Q6") (pin "1") (pinfunction "C_1") (pintype "passive"))
      (node (ref "R56") (pin "1") (pinfunction "1_1") (pintype "passive"))
      (node (ref "ToCubeLayers1") (pin "3") (pinfunction "3_3") (pintype "passive"))
    )
    (net (code "18") (name "/Layer7") (class "Default")
      (node (ref "Q7") (pin "1") (pinfunction "C_1") (pintype "passive"))
      (node (ref "R57") (pin "1") (pinfunction "1_1") (pintype "passive"))
      (node (ref "ToCubeLayers1") (pin "2") (pinfunction "2_2") (pintype "passive"))
    )
    (net (code "19") (name "/Layer8") (class "Default")
      (node (ref "Q8") (pin "1") (pinfunction "C_1") (pintype "passive"))
      (node (ref "R58") (pin "1") (pinfunction "1_1") (pintype "passive"))
      (node (ref "ToCubeLayers1") (pin "1") (pinfunction "1_1") (pintype "passive"))
    )
    (net (code "20") (name "/LayerSel1") (class "Default")
      (node (ref "ArduinoIO1") (pin "13") (pinfunction "13_13") (pintype "passive"))
      (node (ref "R49") (pin "1") (pinfunction "1_1") (pintype "passive"))
    )
    (net (code "21") (name "/LayerSel2") (class "Default")
      (node (ref "ArduinoIO1") (pin "14") (pinfunction "14_14") (pintype "passive"))
      (node (ref "R50") (pin "1") (pinfunction "1_1") (pintype "passive"))
    )
    (net (code "22") (name "/LayerSel3") (class "Default")
      (node (ref "ArduinoIO1") (pin "15") (pinfunction "15_15") (pintype "passive"))
      (node (ref "R59") (pin "1") (pinfunction "1_1") (pintype "passive"))
    )
    (net (code "23") (name "/LayerSel4") (class "Default")
      (node (ref "ArduinoIO1") (pin "16") (pinfunction "16_16") (pintype "passive"))
      (node (ref "R60") (pin "1") (pinfunction "1_1") (pintype "passive"))
    )
    (net (code "24") (name "/LayerSel5") (class "Default")
      (node (ref "ArduinoIO1") (pin "17") (pinfunction "17_17") (pintype "passive"))
      (node (ref "R77") (pin "1") (pinfunction "1_1") (pintype "passive"))
    )
    (net (code "25") (name "/LayerSel6") (class "Default")
      (node (ref "ArduinoIO1") (pin "18") (pinfunction "18_18") (pintype "passive"))
      (node (ref "R78") (pin "1") (pinfunction "1_1") (pintype "passive"))
    )
    (net (code "26") (name "/LayerSel7") (class "Default")
      (node (ref "ArduinoIO1") (pin "19") (pinfunction "19_19") (pintype "passive"))
      (node (ref "R79") (pin "1") (pinfunction "1_1") (pintype "passive"))
    )
    (net (code "27") (name "/LayerSel8") (class "Default")
      (node (ref "ArduinoIO1") (pin "20") (pinfunction "20_20") (pintype "passive"))
      (node (ref "R80") (pin "1") (pinfunction "1_1") (pintype "passive"))
    )
    (net (code "28") (name "/OE") (class "Default")
      (node (ref "ArduinoIO1") (pin "4") (pinfunction "4_4") (pintype "passive"))
      (node (ref "L1") (pin "1") (pinfunction "~{OE}_1") (pintype "input"))
      (node (ref "L2") (pin "1") (pinfunction "~{OE}_1") (pintype "input"))
      (node (ref "L3") (pin "1") (pinfunction "~{OE}_1") (pintype "input"))
      (node (ref "L4") (pin "1") (pinfunction "~{OE}_1") (pintype "input"))
      (node (ref "L5") (pin "1") (pinfunction "~{OE}_1") (pintype "input"))
      (node (ref "L6") (pin "1") (pinfunction "~{OE}_1") (pintype "input"))
      (node (ref "L7") (pin "1") (pinfunction "~{OE}_1") (pintype "input"))
      (node (ref "L8") (pin "1") (pinfunction "~{OE}_1") (pintype "input"))
    )
    (net (code "29") (name "/RowSel1") (class "Default")
      (node (ref "DM1") (pin "15") (pinfunction "~{Y}0_15") (pintype "output"))
      (node (ref "L1") (pin "11") (pinfunction "CLK_11") (pintype "input"))
    )
    (net (code "30") (name "/RowSel2") (class "Default")
      (node (ref "DM1") (pin "14") (pinfunction "~{Y}1_14") (pintype "output"))
      (node (ref "L2") (pin "11") (pinfunction "CLK_11") (pintype "input"))
    )
    (net (code "31") (name "/RowSel3") (class "Default")
      (node (ref "DM1") (pin "13") (pinfunction "~{Y}2_13") (pintype "output"))
      (node (ref "L3") (pin "11") (pinfunction "CLK_11") (pintype "input"))
    )
    (net (code "32") (name "/RowSel4") (class "Default")
      (node (ref "DM1") (pin "12") (pinfunction "~{Y}3_12") (pintype "output"))
      (node (ref "L4") (pin "11") (pinfunction "CLK_11") (pintype "input"))
    )
    (net (code "33") (name "/RowSel5") (class "Default")
      (node (ref "DM1") (pin "11") (pinfunction "~{Y}4_11") (pintype "output"))
      (node (ref "L5") (pin "11") (pinfunction "CLK_11") (pintype "input"))
    )
    (net (code "34") (name "/RowSel6") (class "Default")
      (node (ref "DM1") (pin "10") (pinfunction "~{Y}5_10") (pintype "output"))
      (node (ref "L6") (pin "11") (pinfunction "CLK_11") (pintype "input"))
    )
    (net (code "35") (name "/RowSel7") (class "Default")
      (node (ref "DM1") (pin "9") (pinfunction "~{Y}6_9") (pintype "output"))
      (node (ref "L7") (pin "11") (pinfunction "CLK_11") (pintype "input"))
    )
    (net (code "36") (name "/RowSel8") (class "Default")
      (node (ref "DM1") (pin "7") (pinfunction "~{Y}7_7") (pintype "output"))
      (node (ref "L8") (pin "11") (pinfunction "CLK_11") (pintype "input"))
    )
    (net (code "37") (name "5V") (class "Default")
      (node (ref "C1") (pin "1") (pinfunction "1_1") (pintype "passive"))
      (node (ref "C2") (pin "1") (pinfunction "1_1") (pintype "passive"))
      (node (ref "C3") (pin "1") (pinfunction "1_1") (pintype "passive"))
      (node (ref "C4") (pin "1") (pinfunction "1_1") (pintype "passive"))
      (node (ref "C5") (pin "1") (pinfunction "1_1") (pintype "passive"))
      (node (ref "C6") (pin "1") (pinfunction "1_1") (pintype "passive"))
      (node (ref "C7") (pin "1") (pinfunction "1_1") (pintype "passive"))
      (node (ref "C8") (pin "1") (pinfunction "1_1") (pintype "passive"))
      (node (ref "C9") (pin "1") (pinfunction "1_1") (pintype "passive"))
      (node (ref "CB1") (pin "1") (pinfunction "1_1") (pintype "passive"))
      (node (ref "CB2") (pin "1") (pinfunction "1_1") (pintype "passive"))
      (node (ref "CB3") (pin "1") (pinfunction "1_1") (pintype "passive"))
      (node (ref "DM1") (pin "16") (pinfunction "VCC_16") (pintype "power_in"))
      (node (ref "DM1") (pin "6") (pinfunction "OE1_6") (pintype "input"))
      (node (ref "L1") (pin "20") (pinfunction "VCC_20") (pintype "power_in"))
      (node (ref "L2") (pin "20") (pinfunction "VCC_20") (pintype "power_in"))
      (node (ref "L3") (pin "20") (pinfunction "VCC_20") (pintype "power_in"))
      (node (ref "L4") (pin "20") (pinfunction "VCC_20") (pintype "power_in"))
      (node (ref "L5") (pin "20") (pinfunction "VCC_20") (pintype "power_in"))
      (node (ref "L6") (pin "20") (pinfunction "VCC_20") (pintype "power_in"))
      (node (ref "L7") (pin "20") (pinfunction "VCC_20") (pintype "power_in"))
      (node (ref "L8") (pin "20") (pinfunction "VCC_20") (pintype "power_in"))
      (node (ref "PowerSupply") (pin "1") (pinfunction "1_1") (pintype "passive"))
      (node (ref "R51") (pin "2") (pinfunction "2_2") (pintype "passive"))
      (node (ref "R52") (pin "2") (pinfunction "2_2") (pintype "passive"))
      (node (ref "R53") (pin "2") (pinfunction "2_2") (pintype "passive"))
      (node (ref "R54") (pin "2") (pinfunction "2_2") (pintype "passive"))
      (node (ref "R55") (pin "2") (pinfunction "2_2") (pintype "passive"))
      (node (ref "R56") (pin "2") (pinfunction "2_2") (pintype "passive"))
      (node (ref "R57") (pin "2") (pinfunction "2_2") (pintype "passive"))
      (node (ref "R58") (pin "2") (pinfunction "2_2") (pintype "passive"))
    )
    (net (code "38") (name "GND") (class "Default")
      (node (ref "C1") (pin "2") (pinfunction "2_2") (pintype "passive"))
      (node (ref "C2") (pin "2") (pinfunction "2_2") (pintype "passive"))
      (node (ref "C3") (pin "2") (pinfunction "2_2") (pintype "passive"))
      (node (ref "C4") (pin "2") (pinfunction "2_2") (pintype "passive"))
      (node (ref "C5") (pin "2") (pinfunction "2_2") (pintype "passive"))
      (node (ref "C6") (pin "2") (pinfunction "2_2") (pintype "passive"))
      (node (ref "C7") (pin "2") (pinfunction "2_2") (pintype "passive"))
      (node (ref "C8") (pin "2") (pinfunction "2_2") (pintype "passive"))
      (node (ref "C9") (pin "2") (pinfunction "2_2") (pintype "passive"))
      (node (ref "CB1") (pin "2") (pinfunction "2_2") (pintype "passive"))
      (node (ref "CB2") (pin "2") (pinfunction "2_2") (pintype "passive"))
      (node (ref "CB3") (pin "2") (pinfunction "2_2") (pintype "passive"))
      (node (ref "DM1") (pin "4") (pinfunction "~{OE}2A_4") (pintype "input"))
      (node (ref "DM1") (pin "5") (pinfunction "~{OE}2B_5") (pintype "input"))
      (node (ref "DM1") (pin "8") (pinfunction "GND_8") (pintype "power_in"))
      (node (ref "L1") (pin "10") (pinfunction "GND_10") (pintype "power_in"))
      (node (ref "L2") (pin "10") (pinfunction "GND_10") (pintype "power_in"))
      (node (ref "L3") (pin "10") (pinfunction "GND_10") (pintype "power_in"))
      (node (ref "L4") (pin "10") (pinfunction "GND_10") (pintype "power_in"))
      (node (ref "L5") (pin "10") (pinfunction "GND_10") (pintype "power_in"))
      (node (ref "L6") (pin "10") (pinfunction "GND_10") (pintype "power_in"))
      (node (ref "L7") (pin "10") (pinfunction "GND_10") (pintype "power_in"))
      (node (ref "L8") (pin "10") (pinfunction "GND_10") (pintype "power_in"))
      (node (ref "PowerSupply") (pin "2") (pinfunction "2_2") (pintype "passive"))
      (node (ref "Q1") (pin "3") (pinfunction "E_3") (pintype "passive"))
      (node (ref "Q2") (pin "3") (pinfunction "E_3") (pintype "passive"))
      (node (ref "Q3") (pin "3") (pinfunction "E_3") (pintype "passive"))
      (node (ref "Q4") (pin "3") (pinfunction "E_3") (pintype "passive"))
      (node (ref "Q5") (pin "3") (pinfunction "E_3") (pintype "passive"))
      (node (ref "Q6") (pin "3") (pinfunction "E_3") (pintype "passive"))
      (node (ref "Q7") (pin "3") (pinfunction "E_3") (pintype "passive"))
      (node (ref "Q8") (pin "3") (pinfunction "E_3") (pintype "passive"))
    )
    (net (code "39") (name "Net-(L1-Q1)") (class "Default")
      (node (ref "L1") (pin "19") (pinfunction "Q1_19") (pintype "tri_state"))
      (node (ref "R1") (pin "1") (pinfunction "1_1") (pintype "passive"))
    )
    (net (code "40") (name "Net-(L1-Q2)") (class "Default")
      (node (ref "L1") (pin "18") (pinfunction "Q2_18") (pintype "tri_state"))
      (node (ref "R3") (pin "1") (pinfunction "1_1") (pintype "passive"))
    )
    (net (code "41") (name "Net-(L1-Q3)") (class "Default")
      (node (ref "L1") (pin "17") (pinfunction "Q3_17") (pintype "tri_state"))
      (node (ref "R5") (pin "1") (pinfunction "1_1") (pintype "passive"))
    )
    (net (code "42") (name "Net-(L1-Q4)") (class "Default")
      (node (ref "L1") (pin "16") (pinfunction "Q4_16") (pintype "tri_state"))
      (node (ref "R7") (pin "1") (pinfunction "1_1") (pintype "passive"))
    )
    (net (code "43") (name "Net-(L1-Q5)") (class "Default")
      (node (ref "L1") (pin "15") (pinfunction "Q5_15") (pintype "tri_state"))
      (node (ref "R9") (pin "1") (pinfunction "1_1") (pintype "passive"))
    )
    (net (code "44") (name "Net-(L1-Q6)") (class "Default")
      (node (ref "L1") (pin "14") (pinfunction "Q6_14") (pintype "tri_state"))
      (node (ref "R11") (pin "1") (pinfunction "1_1") (pintype "passive"))
    )
    (net (code "45") (name "Net-(L1-Q7)") (class "Default")
      (node (ref "L1") (pin "13") (pinfunction "Q7_13") (pintype "tri_state"))
      (node (ref "R13") (pin "1") (pinfunction "1_1") (pintype "passive"))
    )
    (net (code "46") (name "Net-(L1-Q8)") (class "Default")
      (node (ref "L1") (pin "12") (pinfunction "Q8_12") (pintype "tri_state"))
      (node (ref "R15") (pin "1") (pinfunction "1_1") (pintype "passive"))
    )
    (net (code "47") (name "Net-(L2-Q1)") (class "Default")
      (node (ref "L2") (pin "19") (pinfunction "Q1_19") (pintype "tri_state"))
      (node (ref "R2") (pin "1") (pinfunction "1_1") (pintype "passive"))
    )
    (net (code "48") (name "Net-(L2-Q2)") (class "Default")
      (node (ref "L2") (pin "18") (pinfunction "Q2_18") (pintype "tri_state"))
      (node (ref "R4") (pin "1") (pinfunction "1_1") (pintype "passive"))
    )
    (net (code "49") (name "Net-(L2-Q3)") (class "Default")
      (node (ref "L2") (pin "17") (pinfunction "Q3_17") (pintype "tri_state"))
      (node (ref "R6") (pin "1") (pinfunction "1_1") (pintype "passive"))
    )
    (net (code "50") (name "Net-(L2-Q4)") (class "Default")
      (node (ref "L2") (pin "16") (pinfunction "Q4_16") (pintype "tri_state"))
      (node (ref "R8") (pin "1") (pinfunction "1_1") (pintype "passive"))
    )
    (net (code "51") (name "Net-(L2-Q5)") (class "Default")
      (node (ref "L2") (pin "15") (pinfunction "Q5_15") (pintype "tri_state"))
      (node (ref "R10") (pin "1") (pinfunction "1_1") (pintype "passive"))
    )
    (net (code "52") (name "Net-(L2-Q6)") (class "Default")
      (node (ref "L2") (pin "14") (pinfunction "Q6_14") (pintype "tri_state"))
      (node (ref "R12") (pin "1") (pinfunction "1_1") (pintype "passive"))
    )
    (net (code "53") (name "Net-(L2-Q7)") (class "Default")
      (node (ref "L2") (pin "13") (pinfunction "Q7_13") (pintype "tri_state"))
      (node (ref "R14") (pin "1") (pinfunction "1_1") (pintype "passive"))
    )
    (net (code "54") (name "Net-(L2-Q8)") (class "Default")
      (node (ref "L2") (pin "12") (pinfunction "Q8_12") (pintype "tri_state"))
      (node (ref "R16") (pin "1") (pinfunction "1_1") (pintype "passive"))
    )
    (net (code "55") (name "Net-(L3-Q1)") (class "Default")
      (node (ref "L3") (pin "19") (pinfunction "Q1_19") (pintype "tri_state"))
      (node (ref "R17") (pin "1") (pinfunction "1_1") (pintype "passive"))
    )
    (net (code "56") (name "Net-(L3-Q2)") (class "Default")
      (node (ref "L3") (pin "18") (pinfunction "Q2_18") (pintype "tri_state"))
      (node (ref "R19") (pin "1") (pinfunction "1_1") (pintype "passive"))
    )
    (net (code "57") (name "Net-(L3-Q3)") (class "Default")
      (node (ref "L3") (pin "17") (pinfunction "Q3_17") (pintype "tri_state"))
      (node (ref "R21") (pin "1") (pinfunction "1_1") (pintype "passive"))
    )
    (net (code "58") (name "Net-(L3-Q4)") (class "Default")
      (node (ref "L3") (pin "16") (pinfunction "Q4_16") (pintype "tri_state"))
      (node (ref "R23") (pin "1") (pinfunction "1_1") (pintype "passive"))
    )
    (net (code "59") (name "Net-(L3-Q5)") (class "Default")
      (node (ref "L3") (pin "15") (pinfunction "Q5_15") (pintype "tri_state"))
      (node (ref "R25") (pin "1") (pinfunction "1_1") (pintype "passive"))
    )
    (net (code "60") (name "Net-(L3-Q6)") (class "Default")
      (node (ref "L3") (pin "14") (pinfunction "Q6_14") (pintype "tri_state"))
      (node (ref "R27") (pin "1") (pinfunction "1_1") (pintype "passive"))
    )
    (net (code "61") (name "Net-(L3-Q7)") (class "Default")
      (node (ref "L3") (pin "13") (pinfunction "Q7_13") (pintype "tri_state"))
      (node (ref "R29") (pin "1") (pinfunction "1_1") (pintype "passive"))
    )
    (net (code "62") (name "Net-(L3-Q8)") (class "Default")
      (node (ref "L3") (pin "12") (pinfunction "Q8_12") (pintype "tri_state"))
      (node (ref "R31") (pin "1") (pinfunction "1_1") (pintype "passive"))
    )
    (net (code "63") (name "Net-(L4-Q1)") (class "Default")
      (node (ref "L4") (pin "19") (pinfunction "Q1_19") (pintype "tri_state"))
      (node (ref "R18") (pin "1") (pinfunction "1_1") (pintype "passive"))
    )
    (net (code "64") (name "Net-(L4-Q2)") (class "Default")
      (node (ref "L4") (pin "18") (pinfunction "Q2_18") (pintype "tri_state"))
      (node (ref "R20") (pin "1") (pinfunction "1_1") (pintype "passive"))
    )
    (net (code "65") (name "Net-(L4-Q3)") (class "Default")
      (node (ref "L4") (pin "17") (pinfunction "Q3_17") (pintype "tri_state"))
      (node (ref "R22") (pin "1") (pinfunction "1_1") (pintype "passive"))
    )
    (net (code "66") (name "Net-(L4-Q4)") (class "Default")
      (node (ref "L4") (pin "16") (pinfunction "Q4_16") (pintype "tri_state"))
      (node (ref "R24") (pin "1") (pinfunction "1_1") (pintype "passive"))
    )
    (net (code "67") (name "Net-(L4-Q5)") (class "Default")
      (node (ref "L4") (pin "15") (pinfunction "Q5_15") (pintype "tri_state"))
      (node (ref "R26") (pin "1") (pinfunction "1_1") (pintype "passive"))
    )
    (net (code "68") (name "Net-(L4-Q6)") (class "Default")
      (node (ref "L4") (pin "14") (pinfunction "Q6_14") (pintype "tri_state"))
      (node (ref "R28") (pin "1") (pinfunction "1_1") (pintype "passive"))
    )
    (net (code "69") (name "Net-(L4-Q7)") (class "Default")
      (node (ref "L4") (pin "13") (pinfunction "Q7_13") (pintype "tri_state"))
      (node (ref "R30") (pin "1") (pinfunction "1_1") (pintype "passive"))
    )
    (net (code "70") (name "Net-(L4-Q8)") (class "Default")
      (node (ref "L4") (pin "12") (pinfunction "Q8_12") (pintype "tri_state"))
      (node (ref "R32") (pin "1") (pinfunction "1_1") (pintype "passive"))
    )
    (net (code "71") (name "Net-(L5-Q1)") (class "Default")
      (node (ref "L5") (pin "19") (pinfunction "Q1_19") (pintype "tri_state"))
      (node (ref "R33") (pin "1") (pinfunction "1_1") (pintype "passive"))
    )
    (net (code "72") (name "Net-(L5-Q2)") (class "Default")
      (node (ref "L5") (pin "18") (pinfunction "Q2_18") (pintype "tri_state"))
      (node (ref "R35") (pin "1") (pinfunction "1_1") (pintype "passive"))
    )
    (net (code "73") (name "Net-(L5-Q3)") (class "Default")
      (node (ref "L5") (pin "17") (pinfunction "Q3_17") (pintype "tri_state"))
      (node (ref "R37") (pin "1") (pinfunction "1_1") (pintype "passive"))
    )
    (net (code "74") (name "Net-(L5-Q4)") (class "Default")
      (node (ref "L5") (pin "16") (pinfunction "Q4_16") (pintype "tri_state"))
      (node (ref "R39") (pin "1") (pinfunction "1_1") (pintype "passive"))
    )
    (net (code "75") (name "Net-(L5-Q5)") (class "Default")
      (node (ref "L5") (pin "15") (pinfunction "Q5_15") (pintype "tri_state"))
      (node (ref "R41") (pin "1") (pinfunction "1_1") (pintype "passive"))
    )
    (net (code "76") (name "Net-(L5-Q6)") (class "Default")
      (node (ref "L5") (pin "14") (pinfunction "Q6_14") (pintype "tri_state"))
      (node (ref "R43") (pin "1") (pinfunction "1_1") (pintype "passive"))
    )
    (net (code "77") (name "Net-(L5-Q7)") (class "Default")
      (node (ref "L5") (pin "13") (pinfunction "Q7_13") (pintype "tri_state"))
      (node (ref "R45") (pin "1") (pinfunction "1_1") (pintype "passive"))
    )
    (net (code "78") (name "Net-(L5-Q8)") (class "Default")
      (node (ref "L5") (pin "12") (pinfunction "Q8_12") (pintype "tri_state"))
      (node (ref "R47") (pin "1") (pinfunction "1_1") (pintype "passive"))
    )
    (net (code "79") (name "Net-(L6-Q1)") (class "Default")
      (node (ref "L6") (pin "19") (pinfunction "Q1_19") (pintype "tri_state"))
      (node (ref "R34") (pin "1") (pinfunction "1_1") (pintype "passive"))
    )
    (net (code "80") (name "Net-(L6-Q2)") (class "Default")
      (node (ref "L6") (pin "18") (pinfunction "Q2_18") (pintype "tri_state"))
      (node (ref "R36") (pin "1") (pinfunction "1_1") (pintype "passive"))
    )
    (net (code "81") (name "Net-(L6-Q3)") (class "Default")
      (node (ref "L6") (pin "17") (pinfunction "Q3_17") (pintype "tri_state"))
      (node (ref "R38") (pin "1") (pinfunction "1_1") (pintype "passive"))
    )
    (net (code "82") (name "Net-(L6-Q4)") (class "Default")
      (node (ref "L6") (pin "16") (pinfunction "Q4_16") (pintype "tri_state"))
      (node (ref "R40") (pin "1") (pinfunction "1_1") (pintype "passive"))
    )
    (net (code "83") (name "Net-(L6-Q5)") (class "Default")
      (node (ref "L6") (pin "15") (pinfunction "Q5_15") (pintype "tri_state"))
      (node (ref "R42") (pin "1") (pinfunction "1_1") (pintype "passive"))
    )
    (net (code "84") (name "Net-(L6-Q6)") (class "Default")
      (node (ref "L6") (pin "14") (pinfunction "Q6_14") (pintype "tri_state"))
      (node (ref "R44") (pin "1") (pinfunction "1_1") (pintype "passive"))
    )
    (net (code "85") (name "Net-(L6-Q7)") (class "Default")
      (node (ref "L6") (pin "13") (pinfunction "Q7_13") (pintype "tri_state"))
      (node (ref "R46") (pin "1") (pinfunction "1_1") (pintype "passive"))
    )
    (net (code "86") (name "Net-(L6-Q8)") (class "Default")
      (node (ref "L6") (pin "12") (pinfunction "Q8_12") (pintype "tri_state"))
      (node (ref "R48") (pin "1") (pinfunction "1_1") (pintype "passive"))
    )
    (net (code "87") (name "Net-(L7-Q1)") (class "Default")
      (node (ref "L7") (pin "19") (pinfunction "Q1_19") (pintype "tri_state"))
      (node (ref "R61") (pin "1") (pinfunction "1_1") (pintype "passive"))
    )
    (net (code "88") (name "Net-(L7-Q2)") (class "Default")
      (node (ref "L7") (pin "18") (pinfunction "Q2_18") (pintype "tri_state"))
      (node (ref "R63") (pin "1") (pinfunction "1_1") (pintype "passive"))
    )
    (net (code "89") (name "Net-(L7-Q3)") (class "Default")
      (node (ref "L7") (pin "17") (pinfunction "Q3_17") (pintype "tri_state"))
      (node (ref "R65") (pin "1") (pinfunction "1_1") (pintype "passive"))
    )
    (net (code "90") (name "Net-(L7-Q4)") (class "Default")
      (node (ref "L7") (pin "16") (pinfunction "Q4_16") (pintype "tri_state"))
      (node (ref "R67") (pin "1") (pinfunction "1_1") (pintype "passive"))
    )
    (net (code "91") (name "Net-(L7-Q5)") (class "Default")
      (node (ref "L7") (pin "15") (pinfunction "Q5_15") (pintype "tri_state"))
      (node (ref "R69") (pin "1") (pinfunction "1_1") (pintype "passive"))
    )
    (net (code "92") (name "Net-(L7-Q6)") (class "Default")
      (node (ref "L7") (pin "14") (pinfunction "Q6_14") (pintype "tri_state"))
      (node (ref "R71") (pin "1") (pinfunction "1_1") (pintype "passive"))
    )
    (net (code "93") (name "Net-(L7-Q7)") (class "Default")
      (node (ref "L7") (pin "13") (pinfunction "Q7_13") (pintype "tri_state"))
      (node (ref "R73") (pin "1") (pinfunction "1_1") (pintype "passive"))
    )
    (net (code "94") (name "Net-(L7-Q8)") (class "Default")
      (node (ref "L7") (pin "12") (pinfunction "Q8_12") (pintype "tri_state"))
      (node (ref "R75") (pin "1") (pinfunction "1_1") (pintype "passive"))
    )
    (net (code "95") (name "Net-(L8-Q1)") (class "Default")
      (node (ref "L8") (pin "19") (pinfunction "Q1_19") (pintype "tri_state"))
      (node (ref "R62") (pin "1") (pinfunction "1_1") (pintype "passive"))
    )
    (net (code "96") (name "Net-(L8-Q2)") (class "Default")
      (node (ref "L8") (pin "18") (pinfunction "Q2_18") (pintype "tri_state"))
      (node (ref "R64") (pin "1") (pinfunction "1_1") (pintype "passive"))
    )
    (net (code "97") (name "Net-(L8-Q3)") (class "Default")
      (node (ref "L8") (pin "17") (pinfunction "Q3_17") (pintype "tri_state"))
      (node (ref "R66") (pin "1") (pinfunction "1_1") (pintype "passive"))
    )
    (net (code "98") (name "Net-(L8-Q4)") (class "Default")
      (node (ref "L8") (pin "16") (pinfunction "Q4_16") (pintype "tri_state"))
      (node (ref "R68") (pin "1") (pinfunction "1_1") (pintype "passive"))
    )
    (net (code "99") (name "Net-(L8-Q5)") (class "Default")
      (node (ref "L8") (pin "15") (pinfunction "Q5_15") (pintype "tri_state"))
      (node (ref "R70") (pin "1") (pinfunction "1_1") (pintype "passive"))
    )
    (net (code "100") (name "Net-(L8-Q6)") (class "Default")
      (node (ref "L8") (pin "14") (pinfunction "Q6_14") (pintype "tri_state"))
      (node (ref "R72") (pin "1") (pinfunction "1_1") (pintype "passive"))
    )
    (net (code "101") (name "Net-(L8-Q7)") (class "Default")
      (node (ref "L8") (pin "13") (pinfunction "Q7_13") (pintype "tri_state"))
      (node (ref "R74") (pin "1") (pinfunction "1_1") (pintype "passive"))
    )
    (net (code "102") (name "Net-(L8-Q8)") (class "Default")
      (node (ref "L8") (pin "12") (pinfunction "Q8_12") (pintype "tri_state"))
      (node (ref "R76") (pin "1") (pinfunction "1_1") (pintype "passive"))
    )
    (net (code "103") (name "Net-(Q1-B)") (class "Default")
      (node (ref "Q1") (pin "2") (pinfunction "B_2") (pintype "passive"))
      (node (ref "R49") (pin "2") (pinfunction "2_2") (pintype "passive"))
    )
    (net (code "104") (name "Net-(Q2-B)") (class "Default")
      (node (ref "Q2") (pin "2") (pinfunction "B_2") (pintype "passive"))
      (node (ref "R50") (pin "2") (pinfunction "2_2") (pintype "passive"))
    )
    (net (code "105") (name "Net-(Q3-B)") (class "Default")
      (node (ref "Q3") (pin "2") (pinfunction "B_2") (pintype "passive"))
      (node (ref "R59") (pin "2") (pinfunction "2_2") (pintype "passive"))
    )
    (net (code "106") (name "Net-(Q4-B)") (class "Default")
      (node (ref "Q4") (pin "2") (pinfunction "B_2") (pintype "passive"))
      (node (ref "R60") (pin "2") (pinfunction "2_2") (pintype "passive"))
    )
    (net (code "107") (name "Net-(Q5-B)") (class "Default")
      (node (ref "Q5") (pin "2") (pinfunction "B_2") (pintype "passive"))
      (node (ref "R77") (pin "2") (pinfunction "2_2") (pintype "passive"))
    )
    (net (code "108") (name "Net-(Q6-B)") (class "Default")
      (node (ref "Q6") (pin "2") (pinfunction "B_2") (pintype "passive"))
      (node (ref "R78") (pin "2") (pinfunction "2_2") (pintype "passive"))
    )
    (net (code "109") (name "Net-(Q7-B)") (class "Default")
      (node (ref "Q7") (pin "2") (pinfunction "B_2") (pintype "passive"))
      (node (ref "R79") (pin "2") (pinfunction "2_2") (pintype "passive"))
    )
    (net (code "110") (name "Net-(Q8-B)") (class "Default")
      (node (ref "Q8") (pin "2") (pinfunction "B_2") (pintype "passive"))
      (node (ref "R80") (pin "2") (pinfunction "2_2") (pintype "passive"))
    )
    (net (code "111") (name "Net-(R1-Pad2)") (class "Default")
      (node (ref "R1") (pin "2") (pinfunction "2_2") (pintype "passive"))
      (node (ref "ToRow1") (pin "1") (pinfunction "1_1") (pintype "passive"))
    )
    (net (code "112") (name "Net-(R2-Pad2)") (class "Default")
      (node (ref "R2") (pin "2") (pinfunction "2_2") (pintype "passive"))
      (node (ref "ToRow2") (pin "1") (pinfunction "1_1") (pintype "passive"))
    )
    (net (code "113") (name "Net-(R3-Pad2)") (class "Default")
      (node (ref "R3") (pin "2") (pinfunction "2_2") (pintype "passive"))
      (node (ref "ToRow1") (pin "2") (pinfunction "2_2") (pintype "passive"))
    )
    (net (code "114") (name "Net-(R4-Pad2)") (class "Default")
      (node (ref "R4") (pin "2") (pinfunction "2_2") (pintype "passive"))
      (node (ref "ToRow2") (pin "2") (pinfunction "2_2") (pintype "passive"))
    )
    (net (code "115") (name "Net-(R5-Pad2)") (class "Default")
      (node (ref "R5") (pin "2") (pinfunction "2_2") (pintype "passive"))
      (node (ref "ToRow1") (pin "3") (pinfunction "3_3") (pintype "passive"))
    )
    (net (code "116") (name "Net-(R6-Pad2)") (class "Default")
      (node (ref "R6") (pin "2") (pinfunction "2_2") (pintype "passive"))
      (node (ref "ToRow2") (pin "3") (pinfunction "3_3") (pintype "passive"))
    )
    (net (code "117") (name "Net-(R7-Pad2)") (class "Default")
      (node (ref "R7") (pin "2") (pinfunction "2_2") (pintype "passive"))
      (node (ref "ToRow1") (pin "4") (pinfunction "4_4") (pintype "passive"))
    )
    (net (code "118") (name "Net-(R8-Pad2)") (class "Default")
      (node (ref "R8") (pin "2") (pinfunction "2_2") (pintype "passive"))
      (node (ref "ToRow2") (pin "4") (pinfunction "4_4") (pintype "passive"))
    )
    (net (code "119") (name "Net-(R9-Pad2)") (class "Default")
      (node (ref "R9") (pin "2") (pinfunction "2_2") (pintype "passive"))
      (node (ref "ToRow1") (pin "5") (pinfunction "5_5") (pintype "passive"))
    )
    (net (code "120") (name "Net-(R10-Pad2)") (class "Default")
      (node (ref "R10") (pin "2") (pinfunction "2_2") (pintype "passive"))
      (node (ref "ToRow2") (pin "5") (pinfunction "5_5") (pintype "passive"))
    )
    (net (code "121") (name "Net-(R11-Pad2)") (class "Default")
      (node (ref "R11") (pin "2") (pinfunction "2_2") (pintype "passive"))
      (node (ref "ToRow1") (pin "6") (pinfunction "6_6") (pintype "passive"))
    )
    (net (code "122") (name "Net-(R12-Pad2)") (class "Default")
      (node (ref "R12") (pin "2") (pinfunction "2_2") (pintype "passive"))
      (node (ref "ToRow2") (pin "6") (pinfunction "6_6") (pintype "passive"))
    )
    (net (code "123") (name "Net-(R13-Pad2)") (class "Default")
      (node (ref "R13") (pin "2") (pinfunction "2_2") (pintype "passive"))
      (node (ref "ToRow1") (pin "7") (pinfunction "7_7") (pintype "passive"))
    )
    (net (code "124") (name "Net-(R14-Pad2)") (class "Default")
      (node (ref "R14") (pin "2") (pinfunction "2_2") (pintype "passive"))
      (node (ref "ToRow2") (pin "7") (pinfunction "7_7") (pintype "passive"))
    )
    (net (code "125") (name "Net-(R15-Pad2)") (class "Default")
      (node (ref "R15") (pin "2") (pinfunction "2_2") (pintype "passive"))
      (node (ref "ToRow1") (pin "8") (pinfunction "8_8") (pintype "passive"))
    )
    (net (code "126") (name "Net-(R16-Pad2)") (class "Default")
      (node (ref "R16") (pin "2") (pinfunction "2_2") (pintype "passive"))
      (node (ref "ToRow2") (pin "8") (pinfunction "8_8") (pintype "passive"))
    )
    (net (code "127") (name "Net-(R17-Pad2)") (class "Default")
      (node (ref "R17") (pin "2") (pinfunction "2_2") (pintype "passive"))
      (node (ref "ToRow3") (pin "1") (pinfunction "1_1") (pintype "passive"))
    )
    (net (code "128") (name "Net-(R18-Pad2)") (class "Default")
      (node (ref "R18") (pin "2") (pinfunction "2_2") (pintype "passive"))
      (node (ref "ToRow4") (pin "1") (pinfunction "1_1") (pintype "passive"))
    )
    (net (code "129") (name "Net-(R19-Pad2)") (class "Default")
      (node (ref "R19") (pin "2") (pinfunction "2_2") (pintype "passive"))
      (node (ref "ToRow3") (pin "2") (pinfunction "2_2") (pintype "passive"))
    )
    (net (code "130") (name "Net-(R20-Pad2)") (class "Default")
      (node (ref "R20") (pin "2") (pinfunction "2_2") (pintype "passive"))
      (node (ref "ToRow4") (pin "2") (pinfunction "2_2") (pintype "passive"))
    )
    (net (code "131") (name "Net-(R21-Pad2)") (class "Default")
      (node (ref "R21") (pin "2") (pinfunction "2_2") (pintype "passive"))
      (node (ref "ToRow3") (pin "3") (pinfunction "3_3") (pintype "passive"))
    )
    (net (code "132") (name "Net-(R22-Pad2)") (class "Default")
      (node (ref "R22") (pin "2") (pinfunction "2_2") (pintype "passive"))
      (node (ref "ToRow4") (pin "3") (pinfunction "3_3") (pintype "passive"))
    )
    (net (code "133") (name "Net-(R23-Pad2)") (class "Default")
      (node (ref "R23") (pin "2") (pinfunction "2_2") (pintype "passive"))
      (node (ref "ToRow3") (pin "4") (pinfunction "4_4") (pintype "passive"))
    )
    (net (code "134") (name "Net-(R24-Pad2)") (class "Default")
      (node (ref "R24") (pin "2") (pinfunction "2_2") (pintype "passive"))
      (node (ref "ToRow4") (pin "4") (pinfunction "4_4") (pintype "passive"))
    )
    (net (code "135") (name "Net-(R25-Pad2)") (class "Default")
      (node (ref "R25") (pin "2") (pinfunction "2_2") (pintype "passive"))
      (node (ref "ToRow3") (pin "5") (pinfunction "5_5") (pintype "passive"))
    )
    (net (code "136") (name "Net-(R26-Pad2)") (class "Default")
      (node (ref "R26") (pin "2") (pinfunction "2_2") (pintype "passive"))
      (node (ref "ToRow4") (pin "5") (pinfunction "5_5") (pintype "passive"))
    )
    (net (code "137") (name "Net-(R27-Pad2)") (class "Default")
      (node (ref "R27") (pin "2") (pinfunction "2_2") (pintype "passive"))
      (node (ref "ToRow3") (pin "6") (pinfunction "6_6") (pintype "passive"))
    )
    (net (code "138") (name "Net-(R28-Pad2)") (class "Default")
      (node (ref "R28") (pin "2") (pinfunction "2_2") (pintype "passive"))
      (node (ref "ToRow4") (pin "6") (pinfunction "6_6") (pintype "passive"))
    )
    (net (code "139") (name "Net-(R29-Pad2)") (class "Default")
      (node (ref "R29") (pin "2") (pinfunction "2_2") (pintype "passive"))
      (node (ref "ToRow3") (pin "7") (pinfunction "7_7") (pintype "passive"))
    )
    (net (code "140") (name "Net-(R30-Pad2)") (class "Default")
      (node (ref "R30") (pin "2") (pinfunction "2_2") (pintype "passive"))
      (node (ref "ToRow4") (pin "7") (pinfunction "7_7") (pintype "passive"))
    )
    (net (code "141") (name "Net-(R31-Pad2)") (class "Default")
      (node (ref "R31") (pin "2") (pinfunction "2_2") (pintype "passive"))
      (node (ref "ToRow3") (pin "8") (pinfunction "8_8") (pintype "passive"))
    )
    (net (code "142") (name "Net-(R32-Pad2)") (class "Default")
      (node (ref "R32") (pin "2") (pinfunction "2_2") (pintype "passive"))
      (node (ref "ToRow4") (pin "8") (pinfunction "8_8") (pintype "passive"))
    )
    (net (code "143") (name "Net-(R33-Pad2)") (class "Default")
      (node (ref "R33") (pin "2") (pinfunction "2_2") (pintype "passive"))
      (node (ref "ToRow5") (pin "1") (pinfunction "1_1") (pintype "passive"))
    )
    (net (code "144") (name "Net-(R34-Pad2)") (class "Default")
      (node (ref "R34") (pin "2") (pinfunction "2_2") (pintype "passive"))
      (node (ref "ToRow6") (pin "1") (pinfunction "1_1") (pintype "passive"))
    )
    (net (code "145") (name "Net-(R35-Pad2)") (class "Default")
      (node (ref "R35") (pin "2") (pinfunction "2_2") (pintype "passive"))
      (node (ref "ToRow5") (pin "2") (pinfunction "2_2") (pintype "passive"))
    )
    (net (code "146") (name "Net-(R36-Pad2)") (class "Default")
      (node (ref "R36") (pin "2") (pinfunction "2_2") (pintype "passive"))
      (node (ref "ToRow6") (pin "2") (pinfunction "2_2") (pintype "passive"))
    )
    (net (code "147") (name "Net-(R37-Pad2)") (class "Default")
      (node (ref "R37") (pin "2") (pinfunction "2_2") (pintype "passive"))
      (node (ref "ToRow5") (pin "3") (pinfunction "3_3") (pintype "passive"))
    )
    (net (code "148") (name "Net-(R38-Pad2)") (class "Default")
      (node (ref "R38") (pin "2") (pinfunction "2_2") (pintype "passive"))
      (node (ref "ToRow6") (pin "3") (pinfunction "3_3") (pintype "passive"))
    )
    (net (code "149") (name "Net-(R39-Pad2)") (class "Default")
      (node (ref "R39") (pin "2") (pinfunction "2_2") (pintype "passive"))
      (node (ref "ToRow5") (pin "4") (pinfunction "4_4") (pintype "passive"))
    )
    (net (code "150") (name "Net-(R40-Pad2)") (class "Default")
      (node (ref "R40") (pin "2") (pinfunction "2_2") (pintype "passive"))
      (node (ref "ToRow6") (pin "4") (pinfunction "4_4") (pintype "passive"))
    )
    (net (code "151") (name "Net-(R41-Pad2)") (class "Default")
      (node (ref "R41") (pin "2") (pinfunction "2_2") (pintype "passive"))
      (node (ref "ToRow5") (pin "5") (pinfunction "5_5") (pintype "passive"))
    )
    (net (code "152") (name "Net-(R42-Pad2)") (class "Default")
      (node (ref "R42") (pin "2") (pinfunction "2_2") (pintype "passive"))
      (node (ref "ToRow6") (pin "5") (pinfunction "5_5") (pintype "passive"))
    )
    (net (code "153") (name "Net-(R43-Pad2)") (class "Default")
      (node (ref "R43") (pin "2") (pinfunction "2_2") (pintype "passive"))
      (node (ref "ToRow5") (pin "6") (pinfunction "6_6") (pintype "passive"))
    )
    (net (code "154") (name "Net-(R44-Pad2)") (class "Default")
      (node (ref "R44") (pin "2") (pinfunction "2_2") (pintype "passive"))
      (node (ref "ToRow6") (pin "6") (pinfunction "6_6") (pintype "passive"))
    )
    (net (code "155") (name "Net-(R45-Pad2)") (class "Default")
      (node (ref "R45") (pin "2") (pinfunction "2_2") (pintype "passive"))
      (node (ref "ToRow5") (pin "7") (pinfunction "7_7") (pintype "passive"))
    )
    (net (code "156") (name "Net-(R46-Pad2)") (class "Default")
      (node (ref "R46") (pin "2") (pinfunction "2_2") (pintype "passive"))
      (node (ref "ToRow6") (pin "7") (pinfunction "7_7") (pintype "passive"))
    )
    (net (code "157") (name "Net-(R47-Pad2)") (class "Default")
      (node (ref "R47") (pin "2") (pinfunction "2_2") (pintype "passive"))
      (node (ref "ToRow5") (pin "8") (pinfunction "8_8") (pintype "passive"))
    )
    (net (code "158") (name "Net-(R48-Pad2)") (class "Default")
      (node (ref "R48") (pin "2") (pinfunction "2_2") (pintype "passive"))
      (node (ref "ToRow6") (pin "8") (pinfunction "8_8") (pintype "passive"))
    )
    (net (code "159") (name "Net-(R61-Pad2)") (class "Default")
      (node (ref "R61") (pin "2") (pinfunction "2_2") (pintype "passive"))
      (node (ref "ToRow7") (pin "1") (pinfunction "1_1") (pintype "passive"))
    )
    (net (code "160") (name "Net-(R62-Pad2)") (class "Default")
      (node (ref "R62") (pin "2") (pinfunction "2_2") (pintype "passive"))
      (node (ref "ToRow8") (pin "1") (pinfunction "1_1") (pintype "passive"))
    )
    (net (code "161") (name "Net-(R63-Pad2)") (class "Default")
      (node (ref "R63") (pin "2") (pinfunction "2_2") (pintype "passive"))
      (node (ref "ToRow7") (pin "2") (pinfunction "2_2") (pintype "passive"))
    )
    (net (code "162") (name "Net-(R64-Pad2)") (class "Default")
      (node (ref "R64") (pin "2") (pinfunction "2_2") (pintype "passive"))
      (node (ref "ToRow8") (pin "2") (pinfunction "2_2") (pintype "passive"))
    )
    (net (code "163") (name "Net-(R65-Pad2)") (class "Default")
      (node (ref "R65") (pin "2") (pinfunction "2_2") (pintype "passive"))
      (node (ref "ToRow7") (pin "3") (pinfunction "3_3") (pintype "passive"))
    )
    (net (code "164") (name "Net-(R66-Pad2)") (class "Default")
      (node (ref "R66") (pin "2") (pinfunction "2_2") (pintype "passive"))
      (node (ref "ToRow8") (pin "3") (pinfunction "3_3") (pintype "passive"))
    )
    (net (code "165") (name "Net-(R67-Pad2)") (class "Default")
      (node (ref "R67") (pin "2") (pinfunction "2_2") (pintype "passive"))
      (node (ref "ToRow7") (pin "4") (pinfunction "4_4") (pintype "passive"))
    )
    (net (code "166") (name "Net-(R68-Pad2)") (class "Default")
      (node (ref "R68") (pin "2") (pinfunction "2_2") (pintype "passive"))
      (node (ref "ToRow8") (pin "4") (pinfunction "4_4") (pintype "passive"))
    )
    (net (code "167") (name "Net-(R69-Pad2)") (class "Default")
      (node (ref "R69") (pin "2") (pinfunction "2_2") (pintype "passive"))
      (node (ref "ToRow7") (pin "5") (pinfunction "5_5") (pintype "passive"))
    )
    (net (code "168") (name "Net-(R70-Pad2)") (class "Default")
      (node (ref "R70") (pin "2") (pinfunction "2_2") (pintype "passive"))
      (node (ref "ToRow8") (pin "5") (pinfunction "5_5") (pintype "passive"))
    )
    (net (code "169") (name "Net-(R71-Pad2)") (class "Default")
      (node (ref "R71") (pin "2") (pinfunction "2_2") (pintype "passive"))
      (node (ref "ToRow7") (pin "6") (pinfunction "6_6") (pintype "passive"))
    )
    (net (code "170") (name "Net-(R72-Pad2)") (class "Default")
      (node (ref "R72") (pin "2") (pinfunction "2_2") (pintype "passive"))
      (node (ref "ToRow8") (pin "6") (pinfunction "6_6") (pintype "passive"))
    )
    (net (code "171") (name "Net-(R73-Pad2)") (class "Default")
      (node (ref "R73") (pin "2") (pinfunction "2_2") (pintype "passive"))
      (node (ref "ToRow7") (pin "7") (pinfunction "7_7") (pintype "passive"))
    )
    (net (code "172") (name "Net-(R74-Pad2)") (class "Default")
      (node (ref "R74") (pin "2") (pinfunction "2_2") (pintype "passive"))
      (node (ref "ToRow8") (pin "7") (pinfunction "7_7") (pintype "passive"))
    )
    (net (code "173") (name "Net-(R75-Pad2)") (class "Default")
      (node (ref "R75") (pin "2") (pinfunction "2_2") (pintype "passive"))
      (node (ref "ToRow7") (pin "8") (pinfunction "8_8") (pintype "passive"))
    )
    (net (code "174") (name "Net-(R76-Pad2)") (class "Default")
      (node (ref "R76") (pin "2") (pinfunction "2_2") (pintype "passive"))
      (node (ref "ToRow8") (pin "8") (pinfunction "8_8") (pintype "passive"))
    )
  )
)
